# Space_Hexapod_hw_v1.net
KiCad netlist of a schematic drawn in EasyEDA Pro
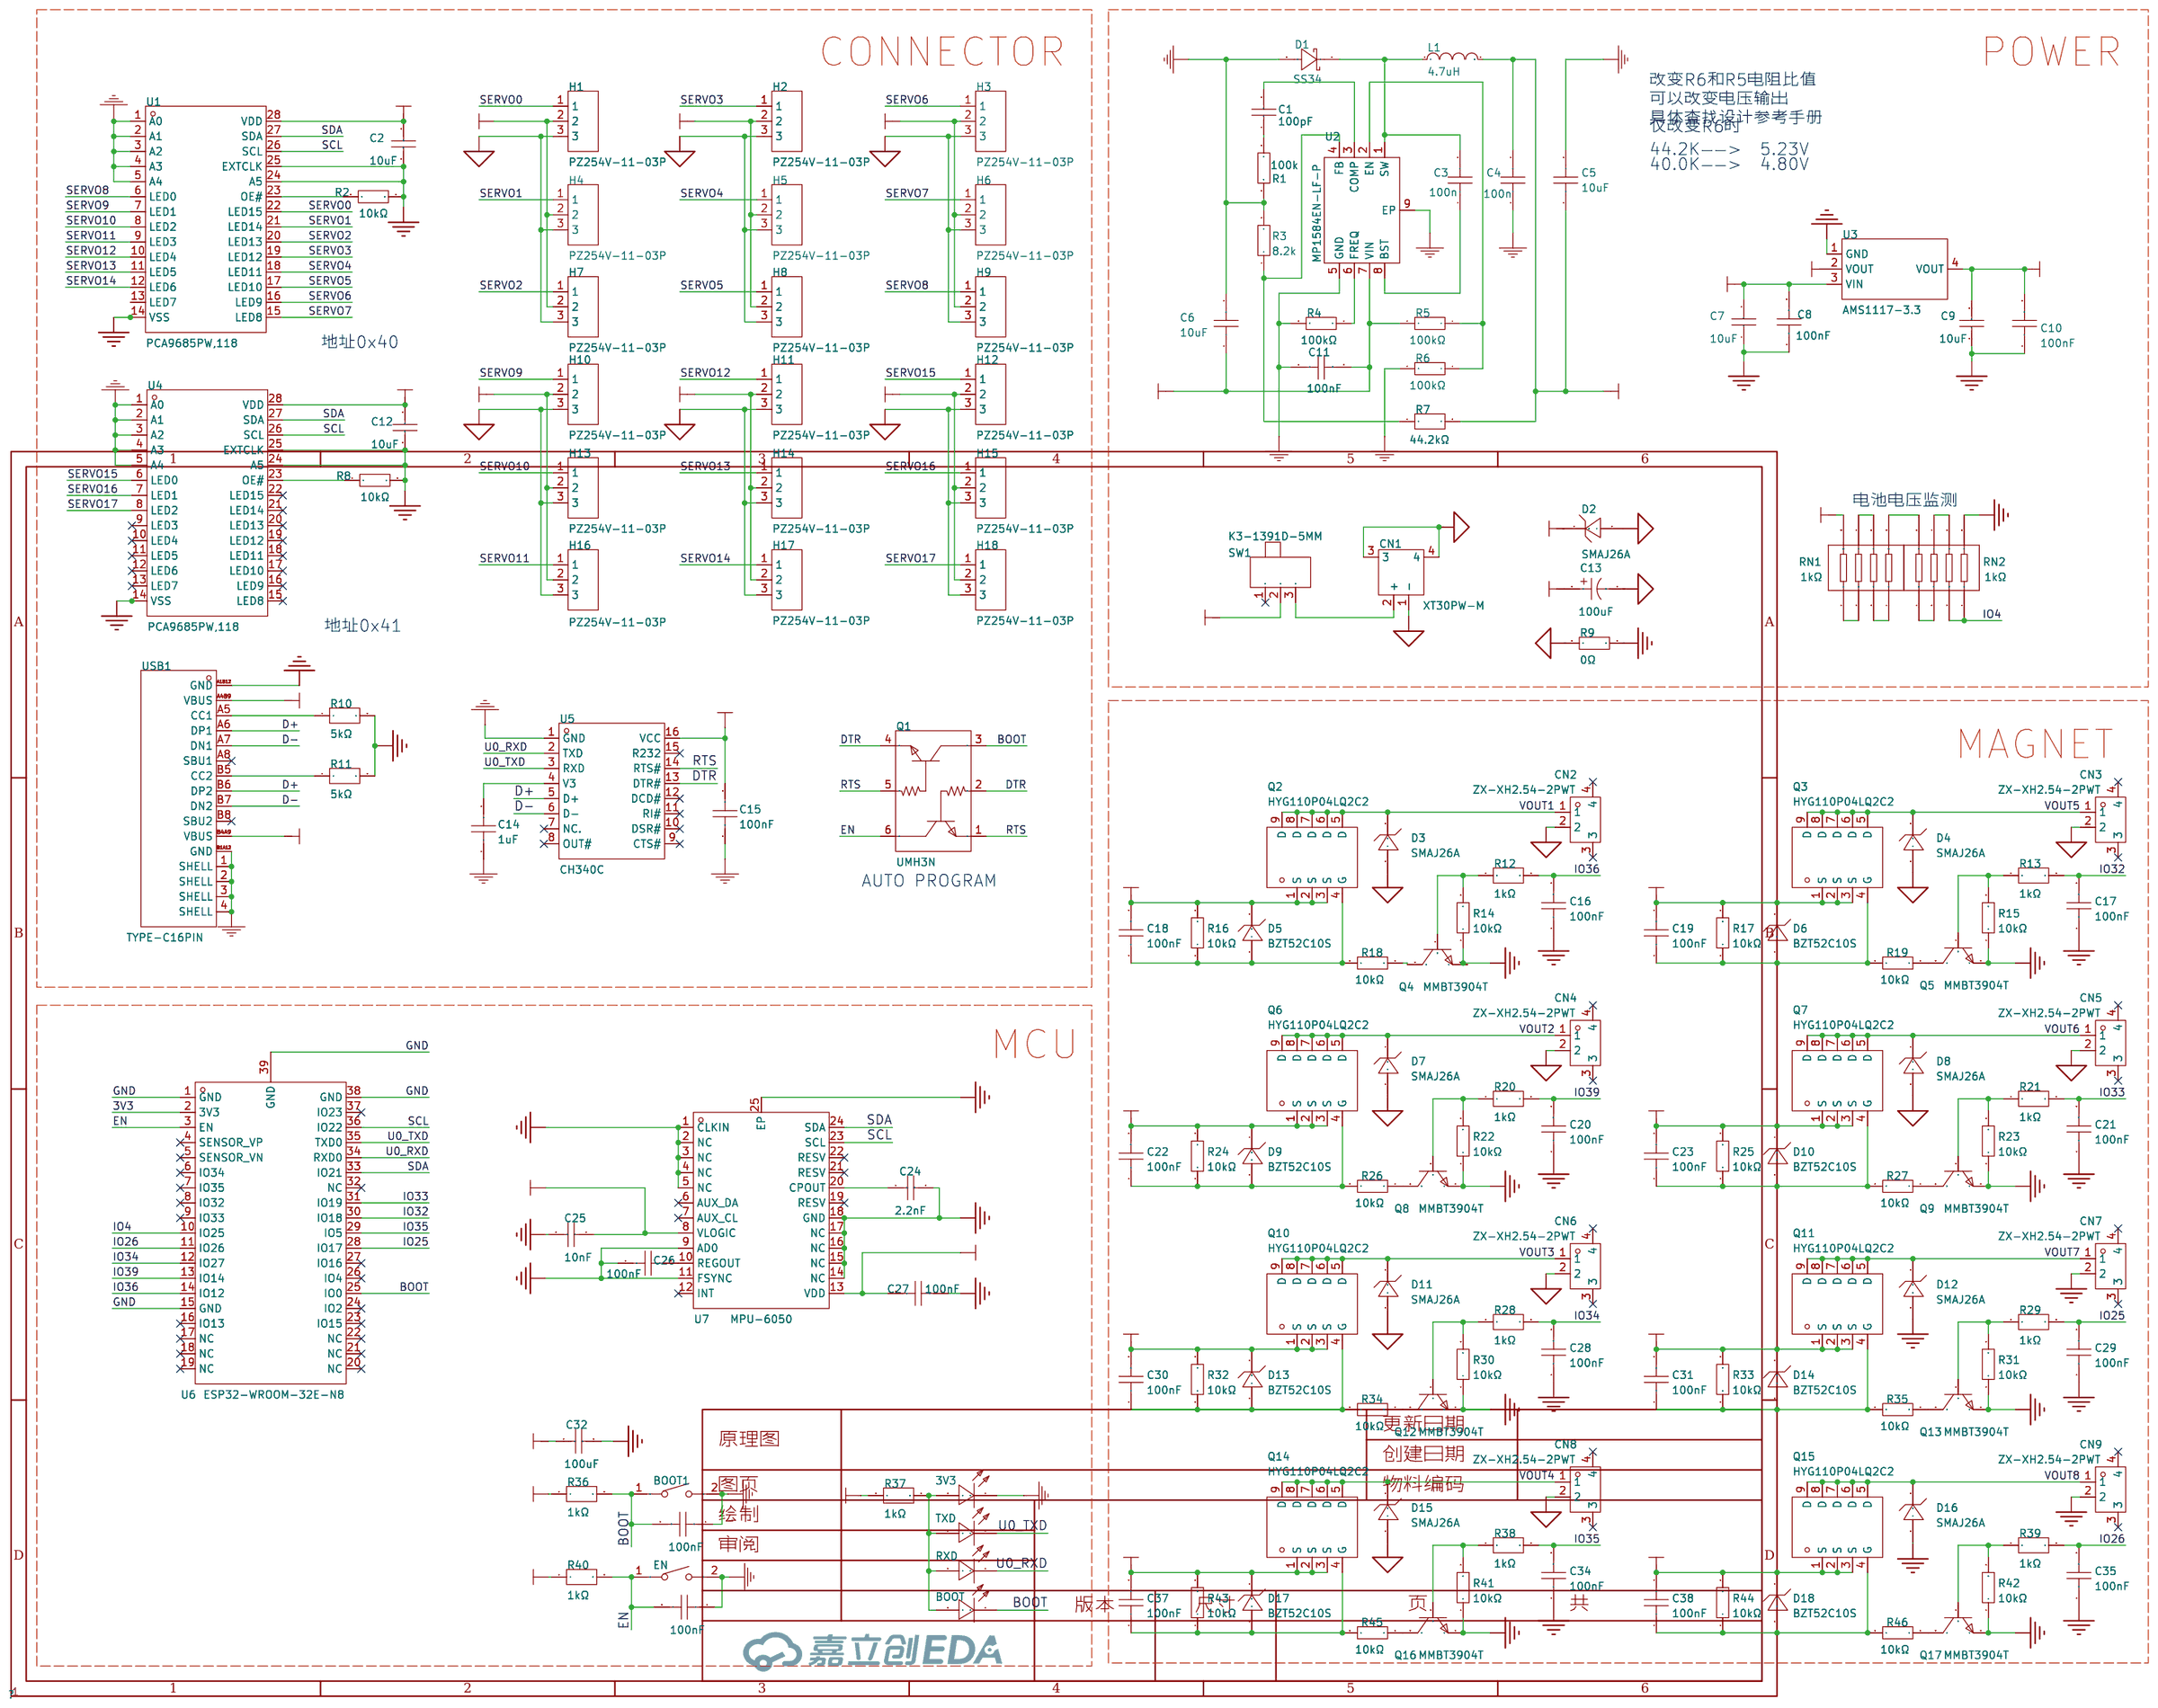
[diagram p0: schematic sheet]

(export (version "E")
  (design (tool "Eeschema 10.0.6"))
  (components
    (comp (ref "3V3")
      (value "NCD0402G1")
      (footprint "easyedapro:LED0402-RD")
      (fields (field (name "Manufacturer") "国星光电"))
      (libsource (lib "easyedapro") (part "FC-F1005UGK-520M5"))
    )
    (comp (ref "BOOT")
      (value "NCD0402G1")
      (footprint "easyedapro:LED0402-RD")
      (fields (field (name "Manufacturer") "国星光电"))
      (libsource (lib "easyedapro") (part "FC-F1005UGK-520M5"))
    )
    (comp (ref "BOOT1")
      (value "TS-1088-AR02016")
      (footprint "easyedapro:SW-SMD_L3.9-W3.0-P4.45")
      (fields (field (name "Manufacturer") "XUNPU(讯普)"))
      (libsource (lib "easyedapro") (part "TS-1088-AR02016"))
    )
    (comp (ref "C1")
      (value "100pF")
      (footprint "easyedapro:C0402")
      (description "容值:100pF;精度:±5%;额定电压:50V;材质(温度系数):C0G;")
      (fields
        (field (name "Manufacturer Part") "GRM1555C1H101JA01D")
        (field (name "Manufacturer") "muRata(村田)")
      )
      (libsource (lib "easyedapro") (part "GRM1555C1H101JA01D"))
    )
    (comp (ref "C2")
      (value "10uF")
      (footprint "easyedapro:C0402")
      (description "容值:10uF;精度:±20%;额定电压:6.3V;材质(温度系数):X5R;")
      (fields
        (field (name "Manufacturer Part") "CL05A106MQ5NUNC")
        (field (name "Manufacturer") "SAMSUNG(三星)")
      )
      (libsource (lib "easyedapro") (part "CL05A106MQ5NUNC"))
    )
    (comp (ref "C3")
      (value "100n")
      (footprint "easyedapro:C0402")
      (description "容值:100nF;精度:±10%;额定电压:50V;材质(温度系数):X7R;")
      (fields
        (field (name "Manufacturer Part") "CL05B104KB54PNC")
        (field (name "Manufacturer") "SAMSUNG(三星)")
      )
      (libsource (lib "easyedapro") (part "CL05B104KB54PNC"))
    )
    (comp (ref "C4")
      (value "100n")
      (footprint "easyedapro:C0402")
      (description "容值:100nF;精度:±10%;额定电压:50V;材质(温度系数):X7R;")
      (fields
        (field (name "Manufacturer Part") "CL05B104KB54PNC")
        (field (name "Manufacturer") "SAMSUNG(三星)")
      )
      (libsource (lib "easyedapro") (part "CL05B104KB54PNC"))
    )
    (comp (ref "C5")
      (value "10uF")
      (footprint "easyedapro:C1206")
      (description "容值:10uF;精度:±10%;额定电压:50V;温度系数:X5R;")
      (fields
        (field (name "Manufacturer Part") "HGC1206R5106K500NSPJ")
        (field (name "Manufacturer") "Chinocera(华瓷)")
      )
      (libsource (lib "easyedapro") (part "HGC1206R5106K500NSPJ"))
    )
    (comp (ref "C6")
      (value "10uF")
      (footprint "easyedapro:C1206")
      (description "容值:10uF;精度:±10%;额定电压:50V;温度系数:X5R;")
      (fields
        (field (name "Manufacturer Part") "HGC1206R5106K500NSPJ")
        (field (name "Manufacturer") "Chinocera(华瓷)")
      )
      (libsource (lib "easyedapro") (part "HGC1206R5106K500NSPJ"))
    )
    (comp (ref "C7")
      (value "10uF")
      (footprint "easyedapro:C0402")
      (description "容值:10uF;精度:±20%;额定电压:6.3V;材质(温度系数):X5R;")
      (fields
        (field (name "Manufacturer Part") "CL05A106MQ5NUNC")
        (field (name "Manufacturer") "SAMSUNG(三星)")
      )
      (libsource (lib "easyedapro") (part "CL05A106MQ5NUNC"))
    )
    (comp (ref "C8")
      (value "100nF")
      (footprint "easyedapro:C0402")
      (description "容值:100nF;精度:±10%;额定电压:16V;材质(温度系数):X7R;")
      (fields
        (field (name "Manufacturer Part") "CC0402KRX7R7BB104")
        (field (name "Manufacturer") "YAGEO(国巨)")
      )
      (libsource (lib "easyedapro") (part "CC0402KRX7R7BB104"))
    )
    (comp (ref "C9")
      (value "10uF")
      (footprint "easyedapro:C0402")
      (description "容值:10uF;精度:±20%;额定电压:6.3V;材质(温度系数):X5R;")
      (fields
        (field (name "Manufacturer Part") "CL05A106MQ5NUNC")
        (field (name "Manufacturer") "SAMSUNG(三星)")
      )
      (libsource (lib "easyedapro") (part "CL05A106MQ5NUNC"))
    )
    (comp (ref "C10")
      (value "100nF")
      (footprint "easyedapro:C0402")
      (description "容值:100nF;精度:±10%;额定电压:16V;材质(温度系数):X7R;")
      (fields
        (field (name "Manufacturer Part") "CC0402KRX7R7BB104")
        (field (name "Manufacturer") "YAGEO(国巨)")
      )
      (libsource (lib "easyedapro") (part "CC0402KRX7R7BB104"))
    )
    (comp (ref "C11")
      (value "100nF")
      (footprint "easyedapro:C0402")
      (description "容值:100nF;精度:±10%;额定电压:50V;材质(温度系数):X7R;")
      (fields
        (field (name "Manufacturer Part") "CL05B104KB54PNC")
        (field (name "Manufacturer") "SAMSUNG(三星)")
      )
      (libsource (lib "easyedapro") (part "CL05B104KB54PNC"))
    )
    (comp (ref "C12")
      (value "10uF")
      (footprint "easyedapro:C0402")
      (description "容值:10uF;精度:±20%;额定电压:6.3V;材质(温度系数):X5R;")
      (fields
        (field (name "Manufacturer Part") "CL05A106MQ5NUNC")
        (field (name "Manufacturer") "SAMSUNG(三星)")
      )
      (libsource (lib "easyedapro") (part "CL05A106MQ5NUNC"))
    )
    (comp (ref "C13")
      (value "100uF")
      (footprint "easyedapro:CAP-SMD_BD6.3-L6.6-W6.6-LS7.6-FD-1")
      (description "容值:100uF;精度:±20%;额定电压:35V;纹波电流:230mA@120Hz;等效串联电阻:600mΩ@100kHz;")
      (fields
        (field (name "Manufacturer Part") "RVE100UF35V67RV0072")
        (field (name "Manufacturer") "KNSCHA(科尼盛)")
      )
      (libsource (lib "easyedapro") (part "RVE100UF35V67RV0072"))
    )
    (comp (ref "C14")
      (value "1uF")
      (footprint "easyedapro:C0402")
      (description "容值:1uF;精度:±10%;额定电压:50V;材质(温度系数):X5R;")
      (fields
        (field (name "Manufacturer Part") "GRM155R61H105KE05D")
        (field (name "Manufacturer") "muRata(村田)")
      )
      (libsource (lib "easyedapro") (part "GRM155R61H105KE05D"))
    )
    (comp (ref "C15")
      (value "100nF")
      (footprint "easyedapro:C0402")
      (description "容值:100nF;精度:±10%;额定电压:50V;材质(温度系数):X7R;")
      (fields
        (field (name "Manufacturer Part") "CL05B104KB54PNC")
        (field (name "Manufacturer") "SAMSUNG(三星)")
      )
      (libsource (lib "easyedapro") (part "CL05B104KB54PNC"))
    )
    (comp (ref "C16")
      (value "100nF")
      (footprint "easyedapro:C0402")
      (description "容值:100nF;精度:±10%;额定电压:50V;材质(温度系数):X7R;")
      (fields
        (field (name "Manufacturer Part") "CL05B104KB54PNC")
        (field (name "Manufacturer") "SAMSUNG(三星)")
      )
      (libsource (lib "easyedapro") (part "CL05B104KB54PNC"))
    )
    (comp (ref "C17")
      (value "100nF")
      (footprint "easyedapro:C0402")
      (description "容值:100nF;精度:±10%;额定电压:50V;材质(温度系数):X7R;")
      (fields
        (field (name "Manufacturer Part") "CL05B104KB54PNC")
        (field (name "Manufacturer") "SAMSUNG(三星)")
      )
      (libsource (lib "easyedapro") (part "CL05B104KB54PNC"))
    )
    (comp (ref "C18")
      (value "100nF")
      (footprint "easyedapro:C0402")
      (description "容值:100nF;精度:±10%;额定电压:50V;材质(温度系数):X7R;")
      (fields
        (field (name "Manufacturer Part") "CL05B104KB54PNC")
        (field (name "Manufacturer") "SAMSUNG(三星)")
      )
      (libsource (lib "easyedapro") (part "CL05B104KB54PNC"))
    )
    (comp (ref "C19")
      (value "100nF")
      (footprint "easyedapro:C0402")
      (description "容值:100nF;精度:±10%;额定电压:50V;材质(温度系数):X7R;")
      (fields
        (field (name "Manufacturer Part") "CL05B104KB54PNC")
        (field (name "Manufacturer") "SAMSUNG(三星)")
      )
      (libsource (lib "easyedapro") (part "CL05B104KB54PNC"))
    )
    (comp (ref "C20")
      (value "100nF")
      (footprint "easyedapro:C0402")
      (description "容值:100nF;精度:±10%;额定电压:50V;材质(温度系数):X7R;")
      (fields
        (field (name "Manufacturer Part") "CL05B104KB54PNC")
        (field (name "Manufacturer") "SAMSUNG(三星)")
      )
      (libsource (lib "easyedapro") (part "CL05B104KB54PNC"))
    )
    (comp (ref "C21")
      (value "100nF")
      (footprint "easyedapro:C0402")
      (description "容值:100nF;精度:±10%;额定电压:50V;材质(温度系数):X7R;")
      (fields
        (field (name "Manufacturer Part") "CL05B104KB54PNC")
        (field (name "Manufacturer") "SAMSUNG(三星)")
      )
      (libsource (lib "easyedapro") (part "CL05B104KB54PNC"))
    )
    (comp (ref "C22")
      (value "100nF")
      (footprint "easyedapro:C0402")
      (description "容值:100nF;精度:±10%;额定电压:50V;材质(温度系数):X7R;")
      (fields
        (field (name "Manufacturer Part") "CL05B104KB54PNC")
        (field (name "Manufacturer") "SAMSUNG(三星)")
      )
      (libsource (lib "easyedapro") (part "CL05B104KB54PNC"))
    )
    (comp (ref "C23")
      (value "100nF")
      (footprint "easyedapro:C0402")
      (description "容值:100nF;精度:±10%;额定电压:50V;材质(温度系数):X7R;")
      (fields
        (field (name "Manufacturer Part") "CL05B104KB54PNC")
        (field (name "Manufacturer") "SAMSUNG(三星)")
      )
      (libsource (lib "easyedapro") (part "CL05B104KB54PNC"))
    )
    (comp (ref "C24")
      (value "2.2nF")
      (footprint "easyedapro:C0402")
      (description "容值:2.2nF;精度:±10%;额定电压:50V;材质(温度系数):X7R;")
      (fields
        (field (name "Manufacturer Part") "CC0402KRX7R9BB222")
        (field (name "Manufacturer") "YAGEO(国巨)")
      )
      (libsource (lib "easyedapro") (part "CC0402KRX7R9BB222"))
    )
    (comp (ref "C25")
      (value "10nF")
      (footprint "easyedapro:C0402")
      (description "容值:10nF;精度:±10%;额定电压:50V;材质(温度系数):X7R;")
      (fields
        (field (name "Manufacturer Part") "CL05B103KB5NNNC")
        (field (name "Manufacturer") "SAMSUNG(三星)")
      )
      (libsource (lib "easyedapro") (part "CL05B103KB5NNNC"))
    )
    (comp (ref "C26")
      (value "100nF")
      (footprint "easyedapro:C0402")
      (description "容值:100nF;精度:±10%;额定电压:50V;材质(温度系数):X7R;")
      (fields
        (field (name "Manufacturer Part") "CL05B104KB54PNC")
        (field (name "Manufacturer") "SAMSUNG(三星)")
      )
      (libsource (lib "easyedapro") (part "CL05B104KB54PNC"))
    )
    (comp (ref "C27")
      (value "100nF")
      (footprint "easyedapro:C0402")
      (description "容值:100nF;精度:±10%;额定电压:50V;材质(温度系数):X7R;")
      (fields
        (field (name "Manufacturer Part") "CL05B104KB54PNC")
        (field (name "Manufacturer") "SAMSUNG(三星)")
      )
      (libsource (lib "easyedapro") (part "CL05B104KB54PNC"))
    )
    (comp (ref "C28")
      (value "100nF")
      (footprint "easyedapro:C0402")
      (description "容值:100nF;精度:±10%;额定电压:50V;材质(温度系数):X7R;")
      (fields
        (field (name "Manufacturer Part") "CL05B104KB54PNC")
        (field (name "Manufacturer") "SAMSUNG(三星)")
      )
      (libsource (lib "easyedapro") (part "CL05B104KB54PNC"))
    )
    (comp (ref "C29")
      (value "100nF")
      (footprint "easyedapro:C0402")
      (description "容值:100nF;精度:±10%;额定电压:50V;材质(温度系数):X7R;")
      (fields
        (field (name "Manufacturer Part") "CL05B104KB54PNC")
        (field (name "Manufacturer") "SAMSUNG(三星)")
      )
      (libsource (lib "easyedapro") (part "CL05B104KB54PNC"))
    )
    (comp (ref "C30")
      (value "100nF")
      (footprint "easyedapro:C0402")
      (description "容值:100nF;精度:±10%;额定电压:50V;材质(温度系数):X7R;")
      (fields
        (field (name "Manufacturer Part") "CL05B104KB54PNC")
        (field (name "Manufacturer") "SAMSUNG(三星)")
      )
      (libsource (lib "easyedapro") (part "CL05B104KB54PNC"))
    )
    (comp (ref "C31")
      (value "100nF")
      (footprint "easyedapro:C0402")
      (description "容值:100nF;精度:±10%;额定电压:50V;材质(温度系数):X7R;")
      (fields
        (field (name "Manufacturer Part") "CL05B104KB54PNC")
        (field (name "Manufacturer") "SAMSUNG(三星)")
      )
      (libsource (lib "easyedapro") (part "CL05B104KB54PNC"))
    )
    (comp (ref "C32")
      (value "100uF")
      (footprint "easyedapro:C1206")
      (description "容值:100uF;精度:±20%;额定电压:6.3V;材质(温度系数):X5R;")
      (fields
        (field (name "Manufacturer Part") "CL31A107MQHNNNE")
        (field (name "Manufacturer") "SAMSUNG(三星)")
      )
      (libsource (lib "easyedapro") (part "CL31A107MQHNNNE"))
    )
    (comp (ref "C33")
      (value "100nF")
      (footprint "easyedapro:C0402")
      (description "容值:100nF;精度:±10%;额定电压:16V;材质(温度系数):X7R;")
      (fields
        (field (name "Manufacturer Part") "CC0402KRX7R7BB104")
        (field (name "Manufacturer") "YAGEO(国巨)")
      )
      (libsource (lib "easyedapro") (part "CC0402KRX7R7BB104"))
    )
    (comp (ref "C34")
      (value "100nF")
      (footprint "easyedapro:C0402")
      (description "容值:100nF;精度:±10%;额定电压:50V;材质(温度系数):X7R;")
      (fields
        (field (name "Manufacturer Part") "CL05B104KB54PNC")
        (field (name "Manufacturer") "SAMSUNG(三星)")
      )
      (libsource (lib "easyedapro") (part "CL05B104KB54PNC"))
    )
    (comp (ref "C35")
      (value "100nF")
      (footprint "easyedapro:C0402")
      (description "容值:100nF;精度:±10%;额定电压:50V;材质(温度系数):X7R;")
      (fields
        (field (name "Manufacturer Part") "CL05B104KB54PNC")
        (field (name "Manufacturer") "SAMSUNG(三星)")
      )
      (libsource (lib "easyedapro") (part "CL05B104KB54PNC"))
    )
    (comp (ref "C36")
      (value "100nF")
      (footprint "easyedapro:C0402")
      (description "容值:100nF;精度:±10%;额定电压:16V;材质(温度系数):X7R;")
      (fields
        (field (name "Manufacturer Part") "CC0402KRX7R7BB104")
        (field (name "Manufacturer") "YAGEO(国巨)")
      )
      (libsource (lib "easyedapro") (part "CC0402KRX7R7BB104"))
    )
    (comp (ref "C37")
      (value "100nF")
      (footprint "easyedapro:C0402")
      (description "容值:100nF;精度:±10%;额定电压:50V;材质(温度系数):X7R;")
      (fields
        (field (name "Manufacturer Part") "CL05B104KB54PNC")
        (field (name "Manufacturer") "SAMSUNG(三星)")
      )
      (libsource (lib "easyedapro") (part "CL05B104KB54PNC"))
    )
    (comp (ref "C38")
      (value "100nF")
      (footprint "easyedapro:C0402")
      (description "容值:100nF;精度:±10%;额定电压:50V;材质(温度系数):X7R;")
      (fields
        (field (name "Manufacturer Part") "CL05B104KB54PNC")
        (field (name "Manufacturer") "SAMSUNG(三星)")
      )
      (libsource (lib "easyedapro") (part "CL05B104KB54PNC"))
    )
    (comp (ref "CN1")
      (value "XT30PW-M")
      (footprint "easyedapro:CONN-TH_XT30PW-M")
      (description "Socket,DCsupply,XT30,male,PIN:2")
      (fields (field (name "Manufacturer") "AMASS(艾迈斯)"))
      (libsource (lib "easyedapro") (part "XT30PW-M"))
    )
    (comp (ref "CN2")
      (value "ZX-XH2.54-2PWT")
      (footprint "easyedapro:CONN-SMD_2P-P2.54_MEGASTAR_ZX-XH2.54-2PWT")
      (description "插针结构:1x2P;间距:2.5mm;安装方式:卧贴;参考系列:XH;总PIN数:2P;排数:1;每排PIN数:2;行距:-;额定电流:-;触头材质:黄铜;触头镀层:锡;工作温度范围:-;")
      (fields (field (name "Manufacturer") "Megastar(兆星)"))
      (libsource (lib "easyedapro") (part "ZX-XH2.54-2PWT"))
    )
    (comp (ref "CN3")
      (value "ZX-XH2.54-2PWT")
      (footprint "easyedapro:CONN-SMD_2P-P2.54_MEGASTAR_ZX-XH2.54-2PWT")
      (description "插针结构:1x2P;间距:2.5mm;安装方式:卧贴;参考系列:XH;总PIN数:2P;排数:1;每排PIN数:2;行距:-;额定电流:-;触头材质:黄铜;触头镀层:锡;工作温度范围:-;")
      (fields (field (name "Manufacturer") "Megastar(兆星)"))
      (libsource (lib "easyedapro") (part "ZX-XH2.54-2PWT"))
    )
    (comp (ref "CN4")
      (value "ZX-XH2.54-2PWT")
      (footprint "easyedapro:CONN-SMD_2P-P2.54_MEGASTAR_ZX-XH2.54-2PWT")
      (description "插针结构:1x2P;间距:2.5mm;安装方式:卧贴;参考系列:XH;总PIN数:2P;排数:1;每排PIN数:2;行距:-;额定电流:-;触头材质:黄铜;触头镀层:锡;工作温度范围:-;")
      (fields (field (name "Manufacturer") "Megastar(兆星)"))
      (libsource (lib "easyedapro") (part "ZX-XH2.54-2PWT"))
    )
    (comp (ref "CN5")
      (value "ZX-XH2.54-2PWT")
      (footprint "easyedapro:CONN-SMD_2P-P2.54_MEGASTAR_ZX-XH2.54-2PWT")
      (description "插针结构:1x2P;间距:2.5mm;安装方式:卧贴;参考系列:XH;总PIN数:2P;排数:1;每排PIN数:2;行距:-;额定电流:-;触头材质:黄铜;触头镀层:锡;工作温度范围:-;")
      (fields (field (name "Manufacturer") "Megastar(兆星)"))
      (libsource (lib "easyedapro") (part "ZX-XH2.54-2PWT"))
    )
    (comp (ref "CN6")
      (value "ZX-XH2.54-2PWT")
      (footprint "easyedapro:CONN-SMD_2P-P2.54_MEGASTAR_ZX-XH2.54-2PWT")
      (description "插针结构:1x2P;间距:2.5mm;安装方式:卧贴;参考系列:XH;总PIN数:2P;排数:1;每排PIN数:2;行距:-;额定电流:-;触头材质:黄铜;触头镀层:锡;工作温度范围:-;")
      (fields (field (name "Manufacturer") "Megastar(兆星)"))
      (libsource (lib "easyedapro") (part "ZX-XH2.54-2PWT"))
    )
    (comp (ref "CN7")
      (value "ZX-XH2.54-2PWT")
      (footprint "easyedapro:CONN-SMD_2P-P2.54_MEGASTAR_ZX-XH2.54-2PWT")
      (description "插针结构:1x2P;间距:2.5mm;安装方式:卧贴;参考系列:XH;总PIN数:2P;排数:1;每排PIN数:2;行距:-;额定电流:-;触头材质:黄铜;触头镀层:锡;工作温度范围:-;")
      (fields (field (name "Manufacturer") "Megastar(兆星)"))
      (libsource (lib "easyedapro") (part "ZX-XH2.54-2PWT"))
    )
    (comp (ref "CN8")
      (value "ZX-XH2.54-2PWT")
      (footprint "easyedapro:CONN-SMD_2P-P2.54_MEGASTAR_ZX-XH2.54-2PWT")
      (description "插针结构:1x2P;间距:2.5mm;安装方式:卧贴;参考系列:XH;总PIN数:2P;排数:1;每排PIN数:2;行距:-;额定电流:-;触头材质:黄铜;触头镀层:锡;工作温度范围:-;")
      (fields (field (name "Manufacturer") "Megastar(兆星)"))
      (libsource (lib "easyedapro") (part "ZX-XH2.54-2PWT"))
    )
    (comp (ref "CN9")
      (value "ZX-XH2.54-2PWT")
      (footprint "easyedapro:CONN-SMD_2P-P2.54_MEGASTAR_ZX-XH2.54-2PWT")
      (description "插针结构:1x2P;间距:2.5mm;安装方式:卧贴;参考系列:XH;总PIN数:2P;排数:1;每排PIN数:2;行距:-;额定电流:-;触头材质:黄铜;触头镀层:锡;工作温度范围:-;")
      (fields (field (name "Manufacturer") "Megastar(兆星)"))
      (libsource (lib "easyedapro") (part "ZX-XH2.54-2PWT"))
    )
    (comp (ref "D1")
      (value "SS34")
      (footprint "easyedapro:SMA_L4.2-W2.7-LS5.0-RD")
      (description "二极管配置:-;正向压降(Vf):550mV@3A;直流反向耐压(Vr):40V;平均整流电流(Io):3A;")
      (fields (field (name "Manufacturer") "KUU"))
      (libsource (lib "easyedapro") (part "SS34_C2891718"))
    )
    (comp (ref "D2")
      (value "SMAJ26A")
      (footprint "easyedapro:SMA_L4.3-W2.6-LS5.1-RD")
      (description "反向截止电压(Vrwm):26V;最大钳位电压:42.1V;峰值脉冲电流(Ipp)@10/1000us:9.5A;击穿电压:28.9V;")
      (fields (field (name "Manufacturer") "GOODWORK(固得沃克)"))
      (libsource (lib "easyedapro") (part "SMAJ26A_C2848697"))
    )
    (comp (ref "D3")
      (value "SMAJ26A")
      (footprint "easyedapro:SMA_L4.3-W2.6-LS5.1-RD")
      (description "反向截止电压(Vrwm):26V;最大钳位电压:42.1V;峰值脉冲电流(Ipp)@10/1000us:9.5A;击穿电压:28.9V;")
      (fields (field (name "Manufacturer") "GOODWORK(固得沃克)"))
      (libsource (lib "easyedapro") (part "SMAJ26A_C2848697"))
    )
    (comp (ref "D4")
      (value "SMAJ26A")
      (footprint "easyedapro:SMA_L4.3-W2.6-LS5.1-RD")
      (description "反向截止电压(Vrwm):26V;最大钳位电压:42.1V;峰值脉冲电流(Ipp)@10/1000us:9.5A;击穿电压:28.9V;")
      (fields (field (name "Manufacturer") "GOODWORK(固得沃克)"))
      (libsource (lib "easyedapro") (part "SMAJ26A_C2848697"))
    )
    (comp (ref "D5")
      (value "BZT52C10S")
      (footprint "easyedapro:SOD-323_L1.6-W1.3-LS2.7-RD")
      (description "二极管配置:独立式;稳压值(标称值):10V;稳压值(范围):9.4V~10.6V;功率:200mW;精度:-;")
      (fields (field (name "Manufacturer") "晶导微电子"))
      (libsource (lib "easyedapro") (part "BZT52C10S_C353563"))
    )
    (comp (ref "D6")
      (value "BZT52C10S")
      (footprint "easyedapro:SOD-323_L1.6-W1.3-LS2.7-RD")
      (description "二极管配置:独立式;稳压值(标称值):10V;稳压值(范围):9.4V~10.6V;功率:200mW;精度:-;")
      (fields (field (name "Manufacturer") "晶导微电子"))
      (libsource (lib "easyedapro") (part "BZT52C10S_C353563"))
    )
    (comp (ref "D7")
      (value "SMAJ26A")
      (footprint "easyedapro:SMA_L4.3-W2.6-LS5.1-RD")
      (description "反向截止电压(Vrwm):26V;最大钳位电压:42.1V;峰值脉冲电流(Ipp)@10/1000us:9.5A;击穿电压:28.9V;")
      (fields (field (name "Manufacturer") "GOODWORK(固得沃克)"))
      (libsource (lib "easyedapro") (part "SMAJ26A_C2848697"))
    )
    (comp (ref "D8")
      (value "SMAJ26A")
      (footprint "easyedapro:SMA_L4.3-W2.6-LS5.1-RD")
      (description "反向截止电压(Vrwm):26V;最大钳位电压:42.1V;峰值脉冲电流(Ipp)@10/1000us:9.5A;击穿电压:28.9V;")
      (fields (field (name "Manufacturer") "GOODWORK(固得沃克)"))
      (libsource (lib "easyedapro") (part "SMAJ26A_C2848697"))
    )
    (comp (ref "D9")
      (value "BZT52C10S")
      (footprint "easyedapro:SOD-323_L1.6-W1.3-LS2.7-RD")
      (description "二极管配置:独立式;稳压值(标称值):10V;稳压值(范围):9.4V~10.6V;功率:200mW;精度:-;")
      (fields (field (name "Manufacturer") "晶导微电子"))
      (libsource (lib "easyedapro") (part "BZT52C10S_C353563"))
    )
    (comp (ref "D10")
      (value "BZT52C10S")
      (footprint "easyedapro:SOD-323_L1.6-W1.3-LS2.7-RD")
      (description "二极管配置:独立式;稳压值(标称值):10V;稳压值(范围):9.4V~10.6V;功率:200mW;精度:-;")
      (fields (field (name "Manufacturer") "晶导微电子"))
      (libsource (lib "easyedapro") (part "BZT52C10S_C353563"))
    )
    (comp (ref "D11")
      (value "SMAJ26A")
      (footprint "easyedapro:SMA_L4.3-W2.6-LS5.1-RD")
      (description "反向截止电压(Vrwm):26V;最大钳位电压:42.1V;峰值脉冲电流(Ipp)@10/1000us:9.5A;击穿电压:28.9V;")
      (fields (field (name "Manufacturer") "GOODWORK(固得沃克)"))
      (libsource (lib "easyedapro") (part "SMAJ26A_C2848697"))
    )
    (comp (ref "D12")
      (value "SMAJ26A")
      (footprint "easyedapro:SMA_L4.3-W2.6-LS5.1-RD")
      (description "反向截止电压(Vrwm):26V;最大钳位电压:42.1V;峰值脉冲电流(Ipp)@10/1000us:9.5A;击穿电压:28.9V;")
      (fields (field (name "Manufacturer") "GOODWORK(固得沃克)"))
      (libsource (lib "easyedapro") (part "SMAJ26A_C2848697"))
    )
    (comp (ref "D13")
      (value "BZT52C10S")
      (footprint "easyedapro:SOD-323_L1.6-W1.3-LS2.7-RD")
      (description "二极管配置:独立式;稳压值(标称值):10V;稳压值(范围):9.4V~10.6V;功率:200mW;精度:-;")
      (fields (field (name "Manufacturer") "晶导微电子"))
      (libsource (lib "easyedapro") (part "BZT52C10S_C353563"))
    )
    (comp (ref "D14")
      (value "BZT52C10S")
      (footprint "easyedapro:SOD-323_L1.6-W1.3-LS2.7-RD")
      (description "二极管配置:独立式;稳压值(标称值):10V;稳压值(范围):9.4V~10.6V;功率:200mW;精度:-;")
      (fields (field (name "Manufacturer") "晶导微电子"))
      (libsource (lib "easyedapro") (part "BZT52C10S_C353563"))
    )
    (comp (ref "D15")
      (value "SMAJ26A")
      (footprint "easyedapro:SMA_L4.3-W2.6-LS5.1-RD")
      (description "反向截止电压(Vrwm):26V;最大钳位电压:42.1V;峰值脉冲电流(Ipp)@10/1000us:9.5A;击穿电压:28.9V;")
      (fields (field (name "Manufacturer") "GOODWORK(固得沃克)"))
      (libsource (lib "easyedapro") (part "SMAJ26A_C2848697"))
    )
    (comp (ref "D16")
      (value "SMAJ26A")
      (footprint "easyedapro:SMA_L4.3-W2.6-LS5.1-RD")
      (description "反向截止电压(Vrwm):26V;最大钳位电压:42.1V;峰值脉冲电流(Ipp)@10/1000us:9.5A;击穿电压:28.9V;")
      (fields (field (name "Manufacturer") "GOODWORK(固得沃克)"))
      (libsource (lib "easyedapro") (part "SMAJ26A_C2848697"))
    )
    (comp (ref "D17")
      (value "BZT52C10S")
      (footprint "easyedapro:SOD-323_L1.6-W1.3-LS2.7-RD")
      (description "二极管配置:独立式;稳压值(标称值):10V;稳压值(范围):9.4V~10.6V;功率:200mW;精度:-;")
      (fields (field (name "Manufacturer") "晶导微电子"))
      (libsource (lib "easyedapro") (part "BZT52C10S_C353563"))
    )
    (comp (ref "D18")
      (value "BZT52C10S")
      (footprint "easyedapro:SOD-323_L1.6-W1.3-LS2.7-RD")
      (description "二极管配置:独立式;稳压值(标称值):10V;稳压值(范围):9.4V~10.6V;功率:200mW;精度:-;")
      (fields (field (name "Manufacturer") "晶导微电子"))
      (libsource (lib "easyedapro") (part "BZT52C10S_C353563"))
    )
    (comp (ref "EN")
      (value "TS-1088-AR02016")
      (footprint "easyedapro:SW-SMD_L3.9-W3.0-P4.45")
      (fields (field (name "Manufacturer") "XUNPU(讯普)"))
      (libsource (lib "easyedapro") (part "TS-1088-AR02016"))
    )
    (comp (ref "H1")
      (value "PZ254V-11-03P")
      (footprint "easyedapro:HDR-TH_3P-P2.54-V-M")
      (fields (field (name "Manufacturer") "XFCN(兴飞)"))
      (libsource (lib "easyedapro") (part "PZ254V-11-03P_C2937625"))
    )
    (comp (ref "H2")
      (value "PZ254V-11-03P")
      (footprint "easyedapro:HDR-TH_3P-P2.54-V-M")
      (fields (field (name "Manufacturer") "XFCN(兴飞)"))
      (libsource (lib "easyedapro") (part "PZ254V-11-03P_C2937625"))
    )
    (comp (ref "H3")
      (value "PZ254V-11-03P")
      (footprint "easyedapro:HDR-TH_3P-P2.54-V-M")
      (fields (field (name "Manufacturer") "XFCN(兴飞)"))
      (libsource (lib "easyedapro") (part "PZ254V-11-03P_C2937625"))
    )
    (comp (ref "H4")
      (value "PZ254V-11-03P")
      (footprint "easyedapro:HDR-TH_3P-P2.54-V-M")
      (fields (field (name "Manufacturer") "XFCN(兴飞)"))
      (libsource (lib "easyedapro") (part "PZ254V-11-03P_C2937625"))
    )
    (comp (ref "H5")
      (value "PZ254V-11-03P")
      (footprint "easyedapro:HDR-TH_3P-P2.54-V-M")
      (fields (field (name "Manufacturer") "XFCN(兴飞)"))
      (libsource (lib "easyedapro") (part "PZ254V-11-03P_C2937625"))
    )
    (comp (ref "H6")
      (value "PZ254V-11-03P")
      (footprint "easyedapro:HDR-TH_3P-P2.54-V-M")
      (fields (field (name "Manufacturer") "XFCN(兴飞)"))
      (libsource (lib "easyedapro") (part "PZ254V-11-03P_C2937625"))
    )
    (comp (ref "H7")
      (value "PZ254V-11-03P")
      (footprint "easyedapro:HDR-TH_3P-P2.54-V-M")
      (fields (field (name "Manufacturer") "XFCN(兴飞)"))
      (libsource (lib "easyedapro") (part "PZ254V-11-03P_C2937625"))
    )
    (comp (ref "H8")
      (value "PZ254V-11-03P")
      (footprint "easyedapro:HDR-TH_3P-P2.54-V-M")
      (fields (field (name "Manufacturer") "XFCN(兴飞)"))
      (libsource (lib "easyedapro") (part "PZ254V-11-03P_C2937625"))
    )
    (comp (ref "H9")
      (value "PZ254V-11-03P")
      (footprint "easyedapro:HDR-TH_3P-P2.54-V-M")
      (fields (field (name "Manufacturer") "XFCN(兴飞)"))
      (libsource (lib "easyedapro") (part "PZ254V-11-03P_C2937625"))
    )
    (comp (ref "H10")
      (value "PZ254V-11-03P")
      (footprint "easyedapro:HDR-TH_3P-P2.54-V-M")
      (fields (field (name "Manufacturer") "XFCN(兴飞)"))
      (libsource (lib "easyedapro") (part "PZ254V-11-03P_C2937625"))
    )
    (comp (ref "H11")
      (value "PZ254V-11-03P")
      (footprint "easyedapro:HDR-TH_3P-P2.54-V-M")
      (fields (field (name "Manufacturer") "XFCN(兴飞)"))
      (libsource (lib "easyedapro") (part "PZ254V-11-03P_C2937625"))
    )
    (comp (ref "H12")
      (value "PZ254V-11-03P")
      (footprint "easyedapro:HDR-TH_3P-P2.54-V-M")
      (fields (field (name "Manufacturer") "XFCN(兴飞)"))
      (libsource (lib "easyedapro") (part "PZ254V-11-03P_C2937625"))
    )
    (comp (ref "H13")
      (value "PZ254V-11-03P")
      (footprint "easyedapro:HDR-TH_3P-P2.54-V-M")
      (fields (field (name "Manufacturer") "XFCN(兴飞)"))
      (libsource (lib "easyedapro") (part "PZ254V-11-03P_C2937625"))
    )
    (comp (ref "H14")
      (value "PZ254V-11-03P")
      (footprint "easyedapro:HDR-TH_3P-P2.54-V-M")
      (fields (field (name "Manufacturer") "XFCN(兴飞)"))
      (libsource (lib "easyedapro") (part "PZ254V-11-03P_C2937625"))
    )
    (comp (ref "H15")
      (value "PZ254V-11-03P")
      (footprint "easyedapro:HDR-TH_3P-P2.54-V-M")
      (fields (field (name "Manufacturer") "XFCN(兴飞)"))
      (libsource (lib "easyedapro") (part "PZ254V-11-03P_C2937625"))
    )
    (comp (ref "H16")
      (value "PZ254V-11-03P")
      (footprint "easyedapro:HDR-TH_3P-P2.54-V-M")
      (fields (field (name "Manufacturer") "XFCN(兴飞)"))
      (libsource (lib "easyedapro") (part "PZ254V-11-03P_C2937625"))
    )
    (comp (ref "H17")
      (value "PZ254V-11-03P")
      (footprint "easyedapro:HDR-TH_3P-P2.54-V-M")
      (fields (field (name "Manufacturer") "XFCN(兴飞)"))
      (libsource (lib "easyedapro") (part "PZ254V-11-03P_C2937625"))
    )
    (comp (ref "H18")
      (value "PZ254V-11-03P")
      (footprint "easyedapro:HDR-TH_3P-P2.54-V-M")
      (fields (field (name "Manufacturer") "XFCN(兴飞)"))
      (libsource (lib "easyedapro") (part "PZ254V-11-03P_C2937625"))
    )
    (comp (ref "L1")
      (value "4.7uH")
      (footprint "easyedapro:IND-SMD_L5.9-W5.2")
      (description "电感值:4.7uH;精度:±20%;额定电流:3A;")
      (fields
        (field (name "Manufacturer Part") "MAPM0530F-4R7M-LF")
        (field (name "Manufacturer") "microgate(麦捷科技)")
      )
      (libsource (lib "easyedapro") (part "MAPM0530F-4R7M-LF"))
    )
    (comp (ref "Q1")
      (value "UMH3N")
      (footprint "easyedapro:SC-70-6_L2.2-W1.3-P0.65-LS2.1-BR")
      (description "晶体管类型:-;集射极击穿电压(Vceo):50V;集电极电流(Ic):100mA;功率(Pd):150mW;直流电流增益(hFE@Ic,Vce):100@1mA,5V;")
      (fields (field (name "Manufacturer") "CJ(江苏长电/长晶)"))
      (libsource (lib "easyedapro") (part "UMH3N"))
    )
    (comp (ref "Q2")
      (value "HYG110P04LQ2C2")
      (footprint "easyedapro:PDFN-8_L5.2-W5.9-P1.27-LS6.2-BL")
      (fields (field (name "Manufacturer") "HUAYI(华羿微)"))
      (libsource (lib "easyedapro") (part "HYG110P04LQ2C2"))
    )
    (comp (ref "Q3")
      (value "HYG110P04LQ2C2")
      (footprint "easyedapro:PDFN-8_L5.2-W5.9-P1.27-LS6.2-BL")
      (fields (field (name "Manufacturer") "HUAYI(华羿微)"))
      (libsource (lib "easyedapro") (part "HYG110P04LQ2C2"))
    )
    (comp (ref "Q4")
      (value "MMBT3904T")
      (footprint "easyedapro:SOT-523-3_L1.6-W0.8-P1.00-LS1.6-BR")
      (description "晶体管类型:NPN;集电极电流(Ic):200mA;集射极击穿电压(Vceo):40V;功率(Pd):250mW;")
      (fields (field (name "Manufacturer") "CJ(江苏长电/长晶)"))
      (libsource (lib "easyedapro") (part "MMBT3904T"))
    )
    (comp (ref "Q5")
      (value "MMBT3904T")
      (footprint "easyedapro:SOT-523-3_L1.6-W0.8-P1.00-LS1.6-BR")
      (description "晶体管类型:NPN;集电极电流(Ic):200mA;集射极击穿电压(Vceo):40V;功率(Pd):250mW;")
      (fields (field (name "Manufacturer") "CJ(江苏长电/长晶)"))
      (libsource (lib "easyedapro") (part "MMBT3904T"))
    )
    (comp (ref "Q6")
      (value "HYG110P04LQ2C2")
      (footprint "easyedapro:PDFN-8_L5.2-W5.9-P1.27-LS6.2-BL")
      (fields (field (name "Manufacturer") "HUAYI(华羿微)"))
      (libsource (lib "easyedapro") (part "HYG110P04LQ2C2"))
    )
    (comp (ref "Q7")
      (value "HYG110P04LQ2C2")
      (footprint "easyedapro:PDFN-8_L5.2-W5.9-P1.27-LS6.2-BL")
      (fields (field (name "Manufacturer") "HUAYI(华羿微)"))
      (libsource (lib "easyedapro") (part "HYG110P04LQ2C2"))
    )
    (comp (ref "Q8")
      (value "MMBT3904T")
      (footprint "easyedapro:SOT-523-3_L1.6-W0.8-P1.00-LS1.6-BR")
      (description "晶体管类型:NPN;集电极电流(Ic):200mA;集射极击穿电压(Vceo):40V;功率(Pd):250mW;")
      (fields (field (name "Manufacturer") "CJ(江苏长电/长晶)"))
      (libsource (lib "easyedapro") (part "MMBT3904T"))
    )
    (comp (ref "Q9")
      (value "MMBT3904T")
      (footprint "easyedapro:SOT-523-3_L1.6-W0.8-P1.00-LS1.6-BR")
      (description "晶体管类型:NPN;集电极电流(Ic):200mA;集射极击穿电压(Vceo):40V;功率(Pd):250mW;")
      (fields (field (name "Manufacturer") "CJ(江苏长电/长晶)"))
      (libsource (lib "easyedapro") (part "MMBT3904T"))
    )
    (comp (ref "Q10")
      (value "HYG110P04LQ2C2")
      (footprint "easyedapro:PDFN-8_L5.2-W5.9-P1.27-LS6.2-BL")
      (fields (field (name "Manufacturer") "HUAYI(华羿微)"))
      (libsource (lib "easyedapro") (part "HYG110P04LQ2C2"))
    )
    (comp (ref "Q11")
      (value "HYG110P04LQ2C2")
      (footprint "easyedapro:PDFN-8_L5.2-W5.9-P1.27-LS6.2-BL")
      (fields (field (name "Manufacturer") "HUAYI(华羿微)"))
      (libsource (lib "easyedapro") (part "HYG110P04LQ2C2"))
    )
    (comp (ref "Q12")
      (value "MMBT3904T")
      (footprint "easyedapro:SOT-523-3_L1.6-W0.8-P1.00-LS1.6-BR")
      (description "晶体管类型:NPN;集电极电流(Ic):200mA;集射极击穿电压(Vceo):40V;功率(Pd):250mW;")
      (fields (field (name "Manufacturer") "CJ(江苏长电/长晶)"))
      (libsource (lib "easyedapro") (part "MMBT3904T"))
    )
    (comp (ref "Q13")
      (value "MMBT3904T")
      (footprint "easyedapro:SOT-523-3_L1.6-W0.8-P1.00-LS1.6-BR")
      (description "晶体管类型:NPN;集电极电流(Ic):200mA;集射极击穿电压(Vceo):40V;功率(Pd):250mW;")
      (fields (field (name "Manufacturer") "CJ(江苏长电/长晶)"))
      (libsource (lib "easyedapro") (part "MMBT3904T"))
    )
    (comp (ref "Q14")
      (value "HYG110P04LQ2C2")
      (footprint "easyedapro:PDFN-8_L5.2-W5.9-P1.27-LS6.2-BL")
      (fields (field (name "Manufacturer") "HUAYI(华羿微)"))
      (libsource (lib "easyedapro") (part "HYG110P04LQ2C2"))
    )
    (comp (ref "Q15")
      (value "HYG110P04LQ2C2")
      (footprint "easyedapro:PDFN-8_L5.2-W5.9-P1.27-LS6.2-BL")
      (fields (field (name "Manufacturer") "HUAYI(华羿微)"))
      (libsource (lib "easyedapro") (part "HYG110P04LQ2C2"))
    )
    (comp (ref "Q16")
      (value "MMBT3904T")
      (footprint "easyedapro:SOT-523-3_L1.6-W0.8-P1.00-LS1.6-BR")
      (description "晶体管类型:NPN;集电极电流(Ic):200mA;集射极击穿电压(Vceo):40V;功率(Pd):250mW;")
      (fields (field (name "Manufacturer") "CJ(江苏长电/长晶)"))
      (libsource (lib "easyedapro") (part "MMBT3904T"))
    )
    (comp (ref "Q17")
      (value "MMBT3904T")
      (footprint "easyedapro:SOT-523-3_L1.6-W0.8-P1.00-LS1.6-BR")
      (description "晶体管类型:NPN;集电极电流(Ic):200mA;集射极击穿电压(Vceo):40V;功率(Pd):250mW;")
      (fields (field (name "Manufacturer") "CJ(江苏长电/长晶)"))
      (libsource (lib "easyedapro") (part "MMBT3904T"))
    )
    (comp (ref "R1")
      (value "100k")
      (footprint "easyedapro:R0402")
      (description "电阻类型:厚膜电阻;阻值:100kΩ;精度:±1%;功率:62.5mW;最大工作电压:50V;温度系数:±100ppm/°C;")
      (fields
        (field (name "Manufacturer Part") "0402WGF1003TCE")
        (field (name "Manufacturer") "UNI-ROYAL(厚声)")
      )
      (libsource (lib "easyedapro") (part "0402WGF1003TCE"))
    )
    (comp (ref "R2")
      (value "10kΩ")
      (footprint "easyedapro:R0402")
      (description "电阻类型:厚膜电阻;阻值:10kΩ;精度:±1%;功率:62.5mW;最大工作电压:50V;温度系数:±100ppm/°C;")
      (fields
        (field (name "Manufacturer Part") "0402WGF1002TCE")
        (field (name "Manufacturer") "UNI-ROYAL(厚声)")
      )
      (libsource (lib "easyedapro") (part "0402WGF1002TCE"))
    )
    (comp (ref "R3")
      (value "8.2k")
      (footprint "easyedapro:R0402")
      (description "电阻类型:厚膜电阻;阻值:8.2kΩ;精度:±1%;功率:62.5mW;最大工作电压:50V;温度系数:±100ppm/°C;")
      (fields
        (field (name "Manufacturer Part") "0402WGF8201TCE")
        (field (name "Manufacturer") "UNI-ROYAL(厚声)")
      )
      (libsource (lib "easyedapro") (part "0402WGF8201TCE"))
    )
    (comp (ref "R4")
      (value "100kΩ")
      (footprint "easyedapro:R0402")
      (description "电阻类型:厚膜电阻;阻值:100kΩ;精度:±1%;功率:62.5mW;最大工作电压:50V;温度系数:±100ppm/°C;")
      (fields
        (field (name "Manufacturer Part") "0402WGF1003TCE")
        (field (name "Manufacturer") "UNI-ROYAL(厚声)")
      )
      (libsource (lib "easyedapro") (part "0402WGF1003TCE"))
    )
    (comp (ref "R5")
      (value "100kΩ")
      (footprint "easyedapro:R0402")
      (description "电阻类型:厚膜电阻;阻值:100kΩ;精度:±1%;功率:62.5mW;最大工作电压:50V;温度系数:±100ppm/°C;")
      (fields
        (field (name "Manufacturer Part") "0402WGF1003TCE")
        (field (name "Manufacturer") "UNI-ROYAL(厚声)")
      )
      (libsource (lib "easyedapro") (part "0402WGF1003TCE"))
    )
    (comp (ref "R6")
      (value "100kΩ")
      (footprint "easyedapro:R0402")
      (description "电阻类型:厚膜电阻;阻值:100kΩ;精度:±1%;功率:62.5mW;最大工作电压:50V;温度系数:±100ppm/°C;")
      (fields
        (field (name "Manufacturer Part") "0402WGF1003TCE")
        (field (name "Manufacturer") "UNI-ROYAL(厚声)")
      )
      (libsource (lib "easyedapro") (part "0402WGF1003TCE"))
    )
    (comp (ref "R7")
      (value "44.2kΩ")
      (footprint "easyedapro:R0402")
      (description "电阻类型:厚膜电阻;阻值:44.2kΩ;精度:±1%;功率:62.5mW;工作电压:50V;温度系数:±100ppm/°C;")
      (fields (field (name "Manufacturer Part") "FRC0402F4422TS") (field (name "Manufacturer") "FOJAN(富捷)"))
      (libsource (lib "easyedapro") (part "FRC0402F4422TS"))
    )
    (comp (ref "R8")
      (value "10kΩ")
      (footprint "easyedapro:R0402")
      (description "电阻类型:厚膜电阻;阻值:10kΩ;精度:±1%;功率:62.5mW;最大工作电压:50V;温度系数:±100ppm/°C;")
      (fields
        (field (name "Manufacturer Part") "0402WGF1002TCE")
        (field (name "Manufacturer") "UNI-ROYAL(厚声)")
      )
      (libsource (lib "easyedapro") (part "0402WGF1002TCE"))
    )
    (comp (ref "R9")
      (value "0Ω")
      (footprint "easyedapro:R0402")
      (description "电阻类型:厚膜电阻;阻值:0Ω;精度:±1%;功率:62.5mW;最大工作电压:50V;温度系数:±800ppm/°C;")
      (fields
        (field (name "Manufacturer Part") "0402WGF0000TCE")
        (field (name "Manufacturer") "UNI-ROYAL(厚声)")
      )
      (libsource (lib "easyedapro") (part "0402WGF0000TCE"))
    )
    (comp (ref "R10")
      (value "5kΩ")
      (footprint "easyedapro:R0402")
      (description "电阻类型:厚膜电阻;阻值:5kΩ;精度:±1%;功率:62.5mW;最大工作电压:50V;温度系数:±100ppm/°C;")
      (fields (field (name "Manufacturer Part") "RC0402FR-075KL") (field (name "Manufacturer") "YAGEO(国巨)"))
      (libsource (lib "easyedapro") (part "RC0402FR-075KL"))
    )
    (comp (ref "R11")
      (value "5kΩ")
      (footprint "easyedapro:R0402")
      (description "电阻类型:厚膜电阻;阻值:5kΩ;精度:±1%;功率:62.5mW;最大工作电压:50V;温度系数:±100ppm/°C;")
      (fields (field (name "Manufacturer Part") "RC0402FR-075KL") (field (name "Manufacturer") "YAGEO(国巨)"))
      (libsource (lib "easyedapro") (part "RC0402FR-075KL"))
    )
    (comp (ref "R12")
      (value "1kΩ")
      (footprint "easyedapro:R0402")
      (description "电阻类型:薄膜电阻;阻值:1kΩ;精度:±0.1%;功率:62.5mW;最大工作电压:50V;温度系数:±25ppm/°C;")
      (fields (field (name "Manufacturer Part") "RT0402BRD071KL") (field (name "Manufacturer") "YAGEO(国巨)"))
      (libsource (lib "easyedapro") (part "RT0402BRD071KL"))
    )
    (comp (ref "R13")
      (value "1kΩ")
      (footprint "easyedapro:R0402")
      (description "电阻类型:薄膜电阻;阻值:1kΩ;精度:±0.1%;功率:62.5mW;最大工作电压:50V;温度系数:±25ppm/°C;")
      (fields (field (name "Manufacturer Part") "RT0402BRD071KL") (field (name "Manufacturer") "YAGEO(国巨)"))
      (libsource (lib "easyedapro") (part "RT0402BRD071KL"))
    )
    (comp (ref "R14")
      (value "10kΩ")
      (footprint "easyedapro:R0402")
      (description "电阻类型:厚膜电阻;阻值:10kΩ;精度:±1%;功率:62.5mW;最大工作电压:50V;温度系数:±100ppm/°C;")
      (fields
        (field (name "Manufacturer Part") "0402WGF1002TCE")
        (field (name "Manufacturer") "UNI-ROYAL(厚声)")
      )
      (libsource (lib "easyedapro") (part "0402WGF1002TCE"))
    )
    (comp (ref "R15")
      (value "10kΩ")
      (footprint "easyedapro:R0402")
      (description "电阻类型:厚膜电阻;阻值:10kΩ;精度:±1%;功率:62.5mW;最大工作电压:50V;温度系数:±100ppm/°C;")
      (fields
        (field (name "Manufacturer Part") "0402WGF1002TCE")
        (field (name "Manufacturer") "UNI-ROYAL(厚声)")
      )
      (libsource (lib "easyedapro") (part "0402WGF1002TCE"))
    )
    (comp (ref "R16")
      (value "10kΩ")
      (footprint "easyedapro:R0402")
      (description "电阻类型:厚膜电阻;阻值:10kΩ;精度:±1%;功率:62.5mW;最大工作电压:50V;温度系数:±100ppm/°C;")
      (fields
        (field (name "Manufacturer Part") "0402WGF1002TCE")
        (field (name "Manufacturer") "UNI-ROYAL(厚声)")
      )
      (libsource (lib "easyedapro") (part "0402WGF1002TCE"))
    )
    (comp (ref "R17")
      (value "10kΩ")
      (footprint "easyedapro:R0402")
      (description "电阻类型:厚膜电阻;阻值:10kΩ;精度:±1%;功率:62.5mW;最大工作电压:50V;温度系数:±100ppm/°C;")
      (fields
        (field (name "Manufacturer Part") "0402WGF1002TCE")
        (field (name "Manufacturer") "UNI-ROYAL(厚声)")
      )
      (libsource (lib "easyedapro") (part "0402WGF1002TCE"))
    )
    (comp (ref "R18")
      (value "10kΩ")
      (footprint "easyedapro:R0402")
      (description "电阻类型:厚膜电阻;阻值:10kΩ;精度:±1%;功率:62.5mW;最大工作电压:50V;温度系数:±100ppm/°C;")
      (fields
        (field (name "Manufacturer Part") "0402WGF1002TCE")
        (field (name "Manufacturer") "UNI-ROYAL(厚声)")
      )
      (libsource (lib "easyedapro") (part "0402WGF1002TCE"))
    )
    (comp (ref "R19")
      (value "10kΩ")
      (footprint "easyedapro:R0402")
      (description "电阻类型:厚膜电阻;阻值:10kΩ;精度:±1%;功率:62.5mW;最大工作电压:50V;温度系数:±100ppm/°C;")
      (fields
        (field (name "Manufacturer Part") "0402WGF1002TCE")
        (field (name "Manufacturer") "UNI-ROYAL(厚声)")
      )
      (libsource (lib "easyedapro") (part "0402WGF1002TCE"))
    )
    (comp (ref "R20")
      (value "1kΩ")
      (footprint "easyedapro:R0402")
      (description "电阻类型:薄膜电阻;阻值:1kΩ;精度:±0.1%;功率:62.5mW;最大工作电压:50V;温度系数:±25ppm/°C;")
      (fields (field (name "Manufacturer Part") "RT0402BRD071KL") (field (name "Manufacturer") "YAGEO(国巨)"))
      (libsource (lib "easyedapro") (part "RT0402BRD071KL"))
    )
    (comp (ref "R21")
      (value "1kΩ")
      (footprint "easyedapro:R0402")
      (description "电阻类型:薄膜电阻;阻值:1kΩ;精度:±0.1%;功率:62.5mW;最大工作电压:50V;温度系数:±25ppm/°C;")
      (fields (field (name "Manufacturer Part") "RT0402BRD071KL") (field (name "Manufacturer") "YAGEO(国巨)"))
      (libsource (lib "easyedapro") (part "RT0402BRD071KL"))
    )
    (comp (ref "R22")
      (value "10kΩ")
      (footprint "easyedapro:R0402")
      (description "电阻类型:厚膜电阻;阻值:10kΩ;精度:±1%;功率:62.5mW;最大工作电压:50V;温度系数:±100ppm/°C;")
      (fields
        (field (name "Manufacturer Part") "0402WGF1002TCE")
        (field (name "Manufacturer") "UNI-ROYAL(厚声)")
      )
      (libsource (lib "easyedapro") (part "0402WGF1002TCE"))
    )
    (comp (ref "R23")
      (value "10kΩ")
      (footprint "easyedapro:R0402")
      (description "电阻类型:厚膜电阻;阻值:10kΩ;精度:±1%;功率:62.5mW;最大工作电压:50V;温度系数:±100ppm/°C;")
      (fields
        (field (name "Manufacturer Part") "0402WGF1002TCE")
        (field (name "Manufacturer") "UNI-ROYAL(厚声)")
      )
      (libsource (lib "easyedapro") (part "0402WGF1002TCE"))
    )
    (comp (ref "R24")
      (value "10kΩ")
      (footprint "easyedapro:R0402")
      (description "电阻类型:厚膜电阻;阻值:10kΩ;精度:±1%;功率:62.5mW;最大工作电压:50V;温度系数:±100ppm/°C;")
      (fields
        (field (name "Manufacturer Part") "0402WGF1002TCE")
        (field (name "Manufacturer") "UNI-ROYAL(厚声)")
      )
      (libsource (lib "easyedapro") (part "0402WGF1002TCE"))
    )
    (comp (ref "R25")
      (value "10kΩ")
      (footprint "easyedapro:R0402")
      (description "电阻类型:厚膜电阻;阻值:10kΩ;精度:±1%;功率:62.5mW;最大工作电压:50V;温度系数:±100ppm/°C;")
      (fields
        (field (name "Manufacturer Part") "0402WGF1002TCE")
        (field (name "Manufacturer") "UNI-ROYAL(厚声)")
      )
      (libsource (lib "easyedapro") (part "0402WGF1002TCE"))
    )
    (comp (ref "R26")
      (value "10kΩ")
      (footprint "easyedapro:R0402")
      (description "电阻类型:厚膜电阻;阻值:10kΩ;精度:±1%;功率:62.5mW;最大工作电压:50V;温度系数:±100ppm/°C;")
      (fields
        (field (name "Manufacturer Part") "0402WGF1002TCE")
        (field (name "Manufacturer") "UNI-ROYAL(厚声)")
      )
      (libsource (lib "easyedapro") (part "0402WGF1002TCE"))
    )
    (comp (ref "R27")
      (value "10kΩ")
      (footprint "easyedapro:R0402")
      (description "电阻类型:厚膜电阻;阻值:10kΩ;精度:±1%;功率:62.5mW;最大工作电压:50V;温度系数:±100ppm/°C;")
      (fields
        (field (name "Manufacturer Part") "0402WGF1002TCE")
        (field (name "Manufacturer") "UNI-ROYAL(厚声)")
      )
      (libsource (lib "easyedapro") (part "0402WGF1002TCE"))
    )
    (comp (ref "R28")
      (value "1kΩ")
      (footprint "easyedapro:R0402")
      (description "电阻类型:薄膜电阻;阻值:1kΩ;精度:±0.1%;功率:62.5mW;最大工作电压:50V;温度系数:±25ppm/°C;")
      (fields (field (name "Manufacturer Part") "RT0402BRD071KL") (field (name "Manufacturer") "YAGEO(国巨)"))
      (libsource (lib "easyedapro") (part "RT0402BRD071KL"))
    )
    (comp (ref "R29")
      (value "1kΩ")
      (footprint "easyedapro:R0402")
      (description "电阻类型:薄膜电阻;阻值:1kΩ;精度:±0.1%;功率:62.5mW;最大工作电压:50V;温度系数:±25ppm/°C;")
      (fields (field (name "Manufacturer Part") "RT0402BRD071KL") (field (name "Manufacturer") "YAGEO(国巨)"))
      (libsource (lib "easyedapro") (part "RT0402BRD071KL"))
    )
    (comp (ref "R30")
      (value "10kΩ")
      (footprint "easyedapro:R0402")
      (description "电阻类型:厚膜电阻;阻值:10kΩ;精度:±1%;功率:62.5mW;最大工作电压:50V;温度系数:±100ppm/°C;")
      (fields
        (field (name "Manufacturer Part") "0402WGF1002TCE")
        (field (name "Manufacturer") "UNI-ROYAL(厚声)")
      )
      (libsource (lib "easyedapro") (part "0402WGF1002TCE"))
    )
    (comp (ref "R31")
      (value "10kΩ")
      (footprint "easyedapro:R0402")
      (description "电阻类型:厚膜电阻;阻值:10kΩ;精度:±1%;功率:62.5mW;最大工作电压:50V;温度系数:±100ppm/°C;")
      (fields
        (field (name "Manufacturer Part") "0402WGF1002TCE")
        (field (name "Manufacturer") "UNI-ROYAL(厚声)")
      )
      (libsource (lib "easyedapro") (part "0402WGF1002TCE"))
    )
    (comp (ref "R32")
      (value "10kΩ")
      (footprint "easyedapro:R0402")
      (description "电阻类型:厚膜电阻;阻值:10kΩ;精度:±1%;功率:62.5mW;最大工作电压:50V;温度系数:±100ppm/°C;")
      (fields
        (field (name "Manufacturer Part") "0402WGF1002TCE")
        (field (name "Manufacturer") "UNI-ROYAL(厚声)")
      )
      (libsource (lib "easyedapro") (part "0402WGF1002TCE"))
    )
    (comp (ref "R33")
      (value "10kΩ")
      (footprint "easyedapro:R0402")
      (description "电阻类型:厚膜电阻;阻值:10kΩ;精度:±1%;功率:62.5mW;最大工作电压:50V;温度系数:±100ppm/°C;")
      (fields
        (field (name "Manufacturer Part") "0402WGF1002TCE")
        (field (name "Manufacturer") "UNI-ROYAL(厚声)")
      )
      (libsource (lib "easyedapro") (part "0402WGF1002TCE"))
    )
    (comp (ref "R34")
      (value "10kΩ")
      (footprint "easyedapro:R0402")
      (description "电阻类型:厚膜电阻;阻值:10kΩ;精度:±1%;功率:62.5mW;最大工作电压:50V;温度系数:±100ppm/°C;")
      (fields
        (field (name "Manufacturer Part") "0402WGF1002TCE")
        (field (name "Manufacturer") "UNI-ROYAL(厚声)")
      )
      (libsource (lib "easyedapro") (part "0402WGF1002TCE"))
    )
    (comp (ref "R35")
      (value "10kΩ")
      (footprint "easyedapro:R0402")
      (description "电阻类型:厚膜电阻;阻值:10kΩ;精度:±1%;功率:62.5mW;最大工作电压:50V;温度系数:±100ppm/°C;")
      (fields
        (field (name "Manufacturer Part") "0402WGF1002TCE")
        (field (name "Manufacturer") "UNI-ROYAL(厚声)")
      )
      (libsource (lib "easyedapro") (part "0402WGF1002TCE"))
    )
    (comp (ref "R36")
      (value "1kΩ")
      (footprint "easyedapro:R0402")
      (description "电阻类型:薄膜电阻;阻值:1kΩ;精度:±0.1%;功率:62.5mW;最大工作电压:50V;温度系数:±25ppm/°C;")
      (fields (field (name "Manufacturer Part") "RT0402BRD071KL") (field (name "Manufacturer") "YAGEO(国巨)"))
      (libsource (lib "easyedapro") (part "RT0402BRD071KL"))
    )
    (comp (ref "R37")
      (value "1kΩ")
      (footprint "easyedapro:R0402")
      (description "电阻类型:薄膜电阻;阻值:1kΩ;精度:±0.1%;功率:62.5mW;最大工作电压:50V;温度系数:±25ppm/°C;")
      (fields (field (name "Manufacturer Part") "RT0402BRD071KL") (field (name "Manufacturer") "YAGEO(国巨)"))
      (libsource (lib "easyedapro") (part "RT0402BRD071KL"))
    )
    (comp (ref "R38")
      (value "1kΩ")
      (footprint "easyedapro:R0402")
      (description "电阻类型:薄膜电阻;阻值:1kΩ;精度:±0.1%;功率:62.5mW;最大工作电压:50V;温度系数:±25ppm/°C;")
      (fields (field (name "Manufacturer Part") "RT0402BRD071KL") (field (name "Manufacturer") "YAGEO(国巨)"))
      (libsource (lib "easyedapro") (part "RT0402BRD071KL"))
    )
    (comp (ref "R39")
      (value "1kΩ")
      (footprint "easyedapro:R0402")
      (description "电阻类型:薄膜电阻;阻值:1kΩ;精度:±0.1%;功率:62.5mW;最大工作电压:50V;温度系数:±25ppm/°C;")
      (fields (field (name "Manufacturer Part") "RT0402BRD071KL") (field (name "Manufacturer") "YAGEO(国巨)"))
      (libsource (lib "easyedapro") (part "RT0402BRD071KL"))
    )
    (comp (ref "R40")
      (value "1kΩ")
      (footprint "easyedapro:R0402")
      (description "电阻类型:薄膜电阻;阻值:1kΩ;精度:±0.1%;功率:62.5mW;最大工作电压:50V;温度系数:±25ppm/°C;")
      (fields (field (name "Manufacturer Part") "RT0402BRD071KL") (field (name "Manufacturer") "YAGEO(国巨)"))
      (libsource (lib "easyedapro") (part "RT0402BRD071KL"))
    )
    (comp (ref "R41")
      (value "10kΩ")
      (footprint "easyedapro:R0402")
      (description "电阻类型:厚膜电阻;阻值:10kΩ;精度:±1%;功率:62.5mW;最大工作电压:50V;温度系数:±100ppm/°C;")
      (fields
        (field (name "Manufacturer Part") "0402WGF1002TCE")
        (field (name "Manufacturer") "UNI-ROYAL(厚声)")
      )
      (libsource (lib "easyedapro") (part "0402WGF1002TCE"))
    )
    (comp (ref "R42")
      (value "10kΩ")
      (footprint "easyedapro:R0402")
      (description "电阻类型:厚膜电阻;阻值:10kΩ;精度:±1%;功率:62.5mW;最大工作电压:50V;温度系数:±100ppm/°C;")
      (fields
        (field (name "Manufacturer Part") "0402WGF1002TCE")
        (field (name "Manufacturer") "UNI-ROYAL(厚声)")
      )
      (libsource (lib "easyedapro") (part "0402WGF1002TCE"))
    )
    (comp (ref "R43")
      (value "10kΩ")
      (footprint "easyedapro:R0402")
      (description "电阻类型:厚膜电阻;阻值:10kΩ;精度:±1%;功率:62.5mW;最大工作电压:50V;温度系数:±100ppm/°C;")
      (fields
        (field (name "Manufacturer Part") "0402WGF1002TCE")
        (field (name "Manufacturer") "UNI-ROYAL(厚声)")
      )
      (libsource (lib "easyedapro") (part "0402WGF1002TCE"))
    )
    (comp (ref "R44")
      (value "10kΩ")
      (footprint "easyedapro:R0402")
      (description "电阻类型:厚膜电阻;阻值:10kΩ;精度:±1%;功率:62.5mW;最大工作电压:50V;温度系数:±100ppm/°C;")
      (fields
        (field (name "Manufacturer Part") "0402WGF1002TCE")
        (field (name "Manufacturer") "UNI-ROYAL(厚声)")
      )
      (libsource (lib "easyedapro") (part "0402WGF1002TCE"))
    )
    (comp (ref "R45")
      (value "10kΩ")
      (footprint "easyedapro:R0402")
      (description "电阻类型:厚膜电阻;阻值:10kΩ;精度:±1%;功率:62.5mW;最大工作电压:50V;温度系数:±100ppm/°C;")
      (fields
        (field (name "Manufacturer Part") "0402WGF1002TCE")
        (field (name "Manufacturer") "UNI-ROYAL(厚声)")
      )
      (libsource (lib "easyedapro") (part "0402WGF1002TCE"))
    )
    (comp (ref "R46")
      (value "10kΩ")
      (footprint "easyedapro:R0402")
      (description "电阻类型:厚膜电阻;阻值:10kΩ;精度:±1%;功率:62.5mW;最大工作电压:50V;温度系数:±100ppm/°C;")
      (fields
        (field (name "Manufacturer Part") "0402WGF1002TCE")
        (field (name "Manufacturer") "UNI-ROYAL(厚声)")
      )
      (libsource (lib "easyedapro") (part "0402WGF1002TCE"))
    )
    (comp (ref "RN1")
      (value "1kΩ")
      (footprint "easyedapro:RES-ARRAY-SMD_0603-8P-L3.2-W1.6-BL")
      (description "电阻器数:4;阻值:1kΩ;精度:±5%;单个元件功率:62.5mW;温度系数:±100ppm/°C;")
      (fields (field (name "Manufacturer Part") "RC-ML08W102JT") (field (name "Manufacturer") "FH(风华)"))
      (libsource (lib "easyedapro") (part "RC-ML08W102JT"))
    )
    (comp (ref "RN2")
      (value "1kΩ")
      (footprint "easyedapro:RES-ARRAY-SMD_0603-8P-L3.2-W1.6-BL")
      (description "电阻器数:4;阻值:1kΩ;精度:±5%;单个元件功率:62.5mW;温度系数:±100ppm/°C;")
      (fields (field (name "Manufacturer Part") "RC-ML08W102JT") (field (name "Manufacturer") "FH(风华)"))
      (libsource (lib "easyedapro") (part "RC-ML08W102JT"))
    )
    (comp (ref "RXD")
      (value "NCD0402G1")
      (footprint "easyedapro:LED0402-RD")
      (fields (field (name "Manufacturer") "国星光电"))
      (libsource (lib "easyedapro") (part "FC-F1005UGK-520M5"))
    )
    (comp (ref "SW1")
      (value "K3-1391D-5MM")
      (footprint "easyedapro:SW-TH_K3-1391D-5MM")
      (description "电路结构:单刀双掷;安装方式:直插;开关颜色:黑色;额定电流(DC):-;额定电压(DC):-;额定电流(AC):3A;额定电压(AC):120V;机械寿命:3万次;")
      (fields (field (name "Manufacturer") "韩国韩荣"))
      (libsource (lib "easyedapro") (part "K3-1391D-5MM"))
    )
    (comp (ref "TXD")
      (value "NCD0402G1")
      (footprint "easyedapro:LED0402-RD")
      (fields (field (name "Manufacturer") "国星光电"))
      (libsource (lib "easyedapro") (part "FC-F1005UGK-520M5"))
    )
    (comp (ref "U1")
      (value "PCA9685PW,118")
      (footprint "easyedapro:TSSOP-28_L9.7-W4.4-P0.65-LS6.4-TL")
      (description "类型:-;输入电压:2.3V~5.5V;开关频率:100kHz~1MHz;通道数:16;输出电压:5.5V;输出电流:25mA;调光:PWM;")
      (fields (field (name "Manufacturer") "NXP(恩智浦)"))
      (libsource (lib "easyedapro") (part "PCA9685PW,118"))
    )
    (comp (ref "U2")
      (value "MP1584EN-LF-P")
      (footprint "easyedapro:SOIC-8_L4.9-W3.9-P1.27-LS6.0-TL-EP-1")
      (description "功能类型:降压型;输出类型:可调;工作电压:4.5V~28V;输出电压:800mV~25V;输出电流:3A;")
      (fields (field (name "Manufacturer") "MPS(芯源)"))
      (libsource (lib "easyedapro") (part "MP1584EN-LF-P"))
    )
    (comp (ref "U3")
      (value "AMS1117-3.3")
      (footprint "easyedapro:SOT-223-3_L6.5-W3.4-P2.30-LS7.0-BR")
      (description "输出类型:固定;最大输入电压:-;输出电压:3.3V;最大输出电流:1A;电源纹波抑制比(PSRR):72dB@(120Hz);输出极性:正极;")
      (fields (field (name "Manufacturer") "AMS"))
      (libsource (lib "easyedapro") (part "AMS1117-3.3"))
    )
    (comp (ref "U4")
      (value "PCA9685PW,118")
      (footprint "easyedapro:TSSOP-28_L9.7-W4.4-P0.65-LS6.4-TL")
      (description "类型:-;输入电压:2.3V~5.5V;开关频率:100kHz~1MHz;通道数:16;输出电压:5.5V;输出电流:25mA;调光:PWM;")
      (fields (field (name "Manufacturer") "NXP(恩智浦)"))
      (libsource (lib "easyedapro") (part "PCA9685PW,118"))
    )
    (comp (ref "U5")
      (value "CH340C")
      (footprint "easyedapro:SOP-16_L10.0-W3.9-P1.27-LS6.0-BL")
      (description "应用功能:收发器;接口协议:USB 2.0;数据速率:2Mbps;")
      (fields (field (name "Manufacturer") "WCH(南京沁恒)"))
      (libsource (lib "easyedapro") (part "CH340C"))
    )
    (comp (ref "U6")
      (value "ESP32-WROOM-32E-N8")
      (footprint "easyedapro:WIFI-SMD_ESP32-WROOM-32E")
      (description "ESP32-WROOM-32E 集成 ESP32-D0WD-V3 芯片，具有?高的稳定性和安全性能。")
      (fields (field (name "Manufacturer") "ESPRESSIF(乐鑫)"))
      (libsource (lib "easyedapro") (part "ESP32-WROOM-32E(8MB)"))
    )
    (comp (ref "U7")
      (value "MPU-6050")
      (footprint "easyedapro:QFN-24_L4.0-W4.0-P0.50-BL-EP2.7")
      (description "传感器类型:加速度计陀螺仪;")
      (fields (field (name "Manufacturer") "TDK InvenSense(应美盛)"))
      (libsource (lib "easyedapro") (part "MPU-6050_C24112"))
    )
    (comp (ref "USB1")
      (value "TYPE-C16PIN")
      (footprint "easyedapro:USB-C-SMD_TYPE-C16PIN")
      (description "连接器类型:Type-C;标准:USB 3.1;公母:母;安装方式:卧贴;触点数量:16P;端口数量:1;额定电流 - 电源:3A;工作温度范围:-40°C~+85°C;")
      (fields (field (name "Manufacturer") "SHOU HAN(首韩)"))
      (libsource (lib "easyedapro") (part "TYPE-C16PIN"))
    )
  )
  (nets
    (net (code "1") (name "/BOOT") (class "Default")
      (node (ref "BOOT") (pin "1") (pinfunction "K_1") (pintype "unspecified"))
      (node (ref "BOOT1") (pin "1") (pinfunction "1_1") (pintype "unspecified"))
      (node (ref "C33") (pin "2") (pinfunction "2_2") (pintype "unspecified"))
      (node (ref "Q1") (pin "3") (pinfunction "C_3") (pintype "unspecified"))
      (node (ref "R36") (pin "2") (pinfunction "2_2") (pintype "unspecified"))
      (node (ref "U6") (pin "25") (pinfunction "IO0_25") (pintype "unspecified"))
    )
    (net (code "2") (name "/D+") (class "Default")
      (node (ref "U5") (pin "5") (pinfunction "D+_5") (pintype "unspecified"))
      (node (ref "USB1") (pin "A6") (pinfunction "DP1_A6") (pintype "unspecified"))
      (node (ref "USB1") (pin "B6") (pinfunction "DP2_B6") (pintype "unspecified"))
    )
    (net (code "3") (name "/D-") (class "Default")
      (node (ref "U5") (pin "6") (pinfunction "D-_6") (pintype "unspecified"))
      (node (ref "USB1") (pin "A7") (pinfunction "DN1_A7") (pintype "unspecified"))
      (node (ref "USB1") (pin "B7") (pinfunction "DN2_B7") (pintype "unspecified"))
    )
    (net (code "4") (name "/DTR") (class "Default")
      (node (ref "Q1") (pin "2") (pinfunction "B_2") (pintype "unspecified"))
      (node (ref "Q1") (pin "4") (pinfunction "E_4") (pintype "unspecified"))
      (node (ref "U5") (pin "13") (pinfunction "DTR#_13") (pintype "unspecified"))
    )
    (net (code "5") (name "/EN") (class "Default")
      (node (ref "C36") (pin "2") (pinfunction "2_2") (pintype "unspecified"))
      (node (ref "EN") (pin "1") (pinfunction "1_1") (pintype "unspecified"))
      (node (ref "Q1") (pin "6") (pinfunction "C_6") (pintype "unspecified"))
      (node (ref "R40") (pin "2") (pinfunction "2_2") (pintype "unspecified"))
      (node (ref "U6") (pin "3") (pinfunction "EN_3") (pintype "unspecified"))
    )
    (net (code "6") (name "/IO4") (class "Default")
      (node (ref "RN2") (pin "3") (pinfunction "3_3") (pintype "input"))
      (node (ref "RN2") (pin "4") (pinfunction "4_4") (pintype "input"))
      (node (ref "U6") (pin "10") (pinfunction "IO25_10") (pintype "unspecified"))
    )
    (net (code "7") (name "/IO25") (class "Default")
      (node (ref "C29") (pin "2") (pinfunction "2_2") (pintype "unspecified"))
      (node (ref "R29") (pin "2") (pinfunction "2_2") (pintype "unspecified"))
      (node (ref "U6") (pin "28") (pinfunction "IO17_28") (pintype "unspecified"))
    )
    (net (code "8") (name "/IO26") (class "Default")
      (node (ref "C35") (pin "2") (pinfunction "2_2") (pintype "unspecified"))
      (node (ref "R39") (pin "2") (pinfunction "2_2") (pintype "unspecified"))
      (node (ref "U6") (pin "11") (pinfunction "IO26_11") (pintype "unspecified"))
    )
    (net (code "9") (name "/IO32") (class "Default")
      (node (ref "C17") (pin "2") (pinfunction "2_2") (pintype "unspecified"))
      (node (ref "R13") (pin "2") (pinfunction "2_2") (pintype "unspecified"))
      (node (ref "U6") (pin "30") (pinfunction "IO18_30") (pintype "unspecified"))
    )
    (net (code "10") (name "/IO33") (class "Default")
      (node (ref "C21") (pin "2") (pinfunction "2_2") (pintype "unspecified"))
      (node (ref "R21") (pin "2") (pinfunction "2_2") (pintype "unspecified"))
      (node (ref "U6") (pin "31") (pinfunction "IO19_31") (pintype "unspecified"))
    )
    (net (code "11") (name "/IO34") (class "Default")
      (node (ref "C28") (pin "2") (pinfunction "2_2") (pintype "unspecified"))
      (node (ref "R28") (pin "2") (pinfunction "2_2") (pintype "unspecified"))
      (node (ref "U6") (pin "12") (pinfunction "IO27_12") (pintype "unspecified"))
    )
    (net (code "12") (name "/IO35") (class "Default")
      (node (ref "C34") (pin "2") (pinfunction "2_2") (pintype "unspecified"))
      (node (ref "R38") (pin "2") (pinfunction "2_2") (pintype "unspecified"))
      (node (ref "U6") (pin "29") (pinfunction "IO5_29") (pintype "unspecified"))
    )
    (net (code "13") (name "/IO36") (class "Default")
      (node (ref "C16") (pin "2") (pinfunction "2_2") (pintype "unspecified"))
      (node (ref "R12") (pin "2") (pinfunction "2_2") (pintype "unspecified"))
      (node (ref "U6") (pin "14") (pinfunction "IO12_14") (pintype "unspecified"))
    )
    (net (code "14") (name "/IO39") (class "Default")
      (node (ref "C20") (pin "2") (pinfunction "2_2") (pintype "unspecified"))
      (node (ref "R20") (pin "2") (pinfunction "2_2") (pintype "unspecified"))
      (node (ref "U6") (pin "13") (pinfunction "IO14_13") (pintype "unspecified"))
    )
    (net (code "15") (name "/RTS") (class "Default")
      (node (ref "Q1") (pin "1") (pinfunction "E_1") (pintype "unspecified"))
      (node (ref "Q1") (pin "5") (pinfunction "B_5") (pintype "unspecified"))
      (node (ref "U5") (pin "14") (pinfunction "RTS#_14") (pintype "unspecified"))
    )
    (net (code "16") (name "/SCL") (class "Default")
      (node (ref "U1") (pin "26") (pinfunction "SCL_26") (pintype "unspecified"))
      (node (ref "U4") (pin "26") (pinfunction "SCL_26") (pintype "unspecified"))
      (node (ref "U6") (pin "36") (pinfunction "IO22_36") (pintype "unspecified"))
      (node (ref "U7") (pin "23") (pinfunction "SCL_23") (pintype "unspecified"))
    )
    (net (code "17") (name "/SDA") (class "Default")
      (node (ref "U1") (pin "27") (pinfunction "SDA_27") (pintype "unspecified"))
      (node (ref "U4") (pin "27") (pinfunction "SDA_27") (pintype "unspecified"))
      (node (ref "U6") (pin "33") (pinfunction "IO21_33") (pintype "unspecified"))
      (node (ref "U7") (pin "24") (pinfunction "SDA_24") (pintype "unspecified"))
    )
    (net (code "18") (name "/SERVO0") (class "Default")
      (node (ref "H1") (pin "1") (pinfunction "1_1") (pintype "unspecified"))
      (node (ref "U1") (pin "22") (pinfunction "LED15_22") (pintype "unspecified"))
    )
    (net (code "19") (name "/SERVO1") (class "Default")
      (node (ref "H4") (pin "1") (pinfunction "1_1") (pintype "unspecified"))
      (node (ref "U1") (pin "21") (pinfunction "LED14_21") (pintype "unspecified"))
    )
    (net (code "20") (name "/SERVO2") (class "Default")
      (node (ref "H7") (pin "1") (pinfunction "1_1") (pintype "unspecified"))
      (node (ref "U1") (pin "20") (pinfunction "LED13_20") (pintype "unspecified"))
    )
    (net (code "21") (name "/SERVO3") (class "Default")
      (node (ref "H2") (pin "1") (pinfunction "1_1") (pintype "unspecified"))
      (node (ref "U1") (pin "19") (pinfunction "LED12_19") (pintype "unspecified"))
    )
    (net (code "22") (name "/SERVO4") (class "Default")
      (node (ref "H5") (pin "1") (pinfunction "1_1") (pintype "unspecified"))
      (node (ref "U1") (pin "18") (pinfunction "LED11_18") (pintype "unspecified"))
    )
    (net (code "23") (name "/SERVO5") (class "Default")
      (node (ref "H8") (pin "1") (pinfunction "1_1") (pintype "unspecified"))
      (node (ref "U1") (pin "17") (pinfunction "LED10_17") (pintype "unspecified"))
    )
    (net (code "24") (name "/SERVO6") (class "Default")
      (node (ref "H3") (pin "1") (pinfunction "1_1") (pintype "unspecified"))
      (node (ref "U1") (pin "16") (pinfunction "LED9_16") (pintype "unspecified"))
    )
    (net (code "25") (name "/SERVO7") (class "Default")
      (node (ref "H6") (pin "1") (pinfunction "1_1") (pintype "unspecified"))
      (node (ref "U1") (pin "15") (pinfunction "LED8_15") (pintype "unspecified"))
    )
    (net (code "26") (name "/SERVO8") (class "Default")
      (node (ref "H9") (pin "1") (pinfunction "1_1") (pintype "unspecified"))
      (node (ref "U1") (pin "6") (pinfunction "LED0_6") (pintype "unspecified"))
    )
    (net (code "27") (name "/SERVO9") (class "Default")
      (node (ref "H10") (pin "1") (pinfunction "1_1") (pintype "unspecified"))
      (node (ref "U1") (pin "7") (pinfunction "LED1_7") (pintype "unspecified"))
    )
    (net (code "28") (name "/SERVO10") (class "Default")
      (node (ref "H13") (pin "1") (pinfunction "1_1") (pintype "unspecified"))
      (node (ref "U1") (pin "8") (pinfunction "LED2_8") (pintype "unspecified"))
    )
    (net (code "29") (name "/SERVO11") (class "Default")
      (node (ref "H16") (pin "1") (pinfunction "1_1") (pintype "unspecified"))
      (node (ref "U1") (pin "9") (pinfunction "LED3_9") (pintype "unspecified"))
    )
    (net (code "30") (name "/SERVO12") (class "Default")
      (node (ref "H11") (pin "1") (pinfunction "1_1") (pintype "unspecified"))
      (node (ref "U1") (pin "10") (pinfunction "LED4_10") (pintype "unspecified"))
    )
    (net (code "31") (name "/SERVO13") (class "Default")
      (node (ref "H14") (pin "1") (pinfunction "1_1") (pintype "unspecified"))
      (node (ref "U1") (pin "11") (pinfunction "LED5_11") (pintype "unspecified"))
    )
    (net (code "32") (name "/SERVO14") (class "Default")
      (node (ref "H17") (pin "1") (pinfunction "1_1") (pintype "unspecified"))
      (node (ref "U1") (pin "12") (pinfunction "LED6_12") (pintype "unspecified"))
    )
    (net (code "33") (name "/SERVO15") (class "Default")
      (node (ref "H12") (pin "1") (pinfunction "1_1") (pintype "unspecified"))
      (node (ref "U4") (pin "6") (pinfunction "LED0_6") (pintype "unspecified"))
    )
    (net (code "34") (name "/SERVO16") (class "Default")
      (node (ref "H15") (pin "1") (pinfunction "1_1") (pintype "unspecified"))
      (node (ref "U4") (pin "7") (pinfunction "LED1_7") (pintype "unspecified"))
    )
    (net (code "35") (name "/SERVO17") (class "Default")
      (node (ref "H18") (pin "1") (pinfunction "1_1") (pintype "unspecified"))
      (node (ref "U4") (pin "8") (pinfunction "LED2_8") (pintype "unspecified"))
    )
    (net (code "36") (name "/U0_RXD") (class "Default")
      (node (ref "RXD") (pin "1") (pinfunction "K_1") (pintype "unspecified"))
      (node (ref "U5") (pin "2") (pinfunction "TXD_2") (pintype "unspecified"))
      (node (ref "U6") (pin "34") (pinfunction "RXD0_34") (pintype "unspecified"))
    )
    (net (code "37") (name "/U0_TXD") (class "Default")
      (node (ref "TXD") (pin "1") (pinfunction "K_1") (pintype "unspecified"))
      (node (ref "U5") (pin "3") (pinfunction "RXD_3") (pintype "unspecified"))
      (node (ref "U6") (pin "35") (pinfunction "TXD0_35") (pintype "unspecified"))
    )
    (net (code "38") (name "/VOUT1") (class "Default")
      (node (ref "CN2") (pin "1") (pinfunction "1_1") (pintype "unspecified"))
      (node (ref "D3") (pin "1") (pinfunction "C_1") (pintype "unspecified"))
      (node (ref "Q2") (pin "5") (pinfunction "D_5") (pintype "unspecified"))
      (node (ref "Q2") (pin "6") (pinfunction "D_6") (pintype "unspecified"))
      (node (ref "Q2") (pin "7") (pinfunction "D_7") (pintype "unspecified"))
      (node (ref "Q2") (pin "8") (pinfunction "D_8") (pintype "unspecified"))
      (node (ref "Q2") (pin "9") (pinfunction "D_9") (pintype "unspecified"))
    )
    (net (code "39") (name "/VOUT2") (class "Default")
      (node (ref "CN4") (pin "1") (pinfunction "1_1") (pintype "unspecified"))
      (node (ref "D7") (pin "1") (pinfunction "C_1") (pintype "unspecified"))
      (node (ref "Q6") (pin "5") (pinfunction "D_5") (pintype "unspecified"))
      (node (ref "Q6") (pin "6") (pinfunction "D_6") (pintype "unspecified"))
      (node (ref "Q6") (pin "7") (pinfunction "D_7") (pintype "unspecified"))
      (node (ref "Q6") (pin "8") (pinfunction "D_8") (pintype "unspecified"))
      (node (ref "Q6") (pin "9") (pinfunction "D_9") (pintype "unspecified"))
    )
    (net (code "40") (name "/VOUT3") (class "Default")
      (node (ref "CN6") (pin "1") (pinfunction "1_1") (pintype "unspecified"))
      (node (ref "D11") (pin "1") (pinfunction "C_1") (pintype "unspecified"))
      (node (ref "Q10") (pin "5") (pinfunction "D_5") (pintype "unspecified"))
      (node (ref "Q10") (pin "6") (pinfunction "D_6") (pintype "unspecified"))
      (node (ref "Q10") (pin "7") (pinfunction "D_7") (pintype "unspecified"))
      (node (ref "Q10") (pin "8") (pinfunction "D_8") (pintype "unspecified"))
      (node (ref "Q10") (pin "9") (pinfunction "D_9") (pintype "unspecified"))
    )
    (net (code "41") (name "/VOUT4") (class "Default")
      (node (ref "CN8") (pin "1") (pinfunction "1_1") (pintype "unspecified"))
      (node (ref "D15") (pin "1") (pinfunction "C_1") (pintype "unspecified"))
      (node (ref "Q14") (pin "5") (pinfunction "D_5") (pintype "unspecified"))
      (node (ref "Q14") (pin "6") (pinfunction "D_6") (pintype "unspecified"))
      (node (ref "Q14") (pin "7") (pinfunction "D_7") (pintype "unspecified"))
      (node (ref "Q14") (pin "8") (pinfunction "D_8") (pintype "unspecified"))
      (node (ref "Q14") (pin "9") (pinfunction "D_9") (pintype "unspecified"))
    )
    (net (code "42") (name "/VOUT5") (class "Default")
      (node (ref "CN3") (pin "1") (pinfunction "1_1") (pintype "unspecified"))
      (node (ref "D4") (pin "1") (pinfunction "C_1") (pintype "unspecified"))
      (node (ref "Q3") (pin "5") (pinfunction "D_5") (pintype "unspecified"))
      (node (ref "Q3") (pin "6") (pinfunction "D_6") (pintype "unspecified"))
      (node (ref "Q3") (pin "7") (pinfunction "D_7") (pintype "unspecified"))
      (node (ref "Q3") (pin "8") (pinfunction "D_8") (pintype "unspecified"))
      (node (ref "Q3") (pin "9") (pinfunction "D_9") (pintype "unspecified"))
    )
    (net (code "43") (name "/VOUT6") (class "Default")
      (node (ref "CN5") (pin "1") (pinfunction "1_1") (pintype "unspecified"))
      (node (ref "D8") (pin "1") (pinfunction "C_1") (pintype "unspecified"))
      (node (ref "Q7") (pin "5") (pinfunction "D_5") (pintype "unspecified"))
      (node (ref "Q7") (pin "6") (pinfunction "D_6") (pintype "unspecified"))
      (node (ref "Q7") (pin "7") (pinfunction "D_7") (pintype "unspecified"))
      (node (ref "Q7") (pin "8") (pinfunction "D_8") (pintype "unspecified"))
      (node (ref "Q7") (pin "9") (pinfunction "D_9") (pintype "unspecified"))
    )
    (net (code "44") (name "/VOUT7") (class "Default")
      (node (ref "CN7") (pin "1") (pinfunction "1_1") (pintype "unspecified"))
      (node (ref "D12") (pin "1") (pinfunction "C_1") (pintype "unspecified"))
      (node (ref "Q11") (pin "5") (pinfunction "D_5") (pintype "unspecified"))
      (node (ref "Q11") (pin "6") (pinfunction "D_6") (pintype "unspecified"))
      (node (ref "Q11") (pin "7") (pinfunction "D_7") (pintype "unspecified"))
      (node (ref "Q11") (pin "8") (pinfunction "D_8") (pintype "unspecified"))
      (node (ref "Q11") (pin "9") (pinfunction "D_9") (pintype "unspecified"))
    )
    (net (code "45") (name "/VOUT8") (class "Default")
      (node (ref "CN9") (pin "1") (pinfunction "1_1") (pintype "unspecified"))
      (node (ref "D16") (pin "1") (pinfunction "C_1") (pintype "unspecified"))
      (node (ref "Q15") (pin "5") (pinfunction "D_5") (pintype "unspecified"))
      (node (ref "Q15") (pin "6") (pinfunction "D_6") (pintype "unspecified"))
      (node (ref "Q15") (pin "7") (pinfunction "D_7") (pintype "unspecified"))
      (node (ref "Q15") (pin "8") (pinfunction "D_8") (pintype "unspecified"))
      (node (ref "Q15") (pin "9") (pinfunction "D_9") (pintype "unspecified"))
    )
    (net (code "46") (name "3V3") (class "Default")
      (node (ref "C10") (pin "2") (pinfunction "2_2") (pintype "unspecified"))
      (node (ref "C12") (pin "2") (pinfunction "2_2") (pintype "input"))
      (node (ref "C15") (pin "2") (pinfunction "2_2") (pintype "unspecified"))
      (node (ref "C2") (pin "2") (pinfunction "2_2") (pintype "input"))
      (node (ref "C25") (pin "1") (pinfunction "1_1") (pintype "input"))
      (node (ref "C27") (pin "2") (pinfunction "2_2") (pintype "unspecified"))
      (node (ref "C32") (pin "1") (pinfunction "1_1") (pintype "input"))
      (node (ref "C9") (pin "2") (pinfunction "2_2") (pintype "input"))
      (node (ref "R36") (pin "1") (pinfunction "1_1") (pintype "unspecified"))
      (node (ref "R37") (pin "1") (pinfunction "1_1") (pintype "unspecified"))
      (node (ref "R40") (pin "1") (pinfunction "1_1") (pintype "unspecified"))
      (node (ref "U1") (pin "28") (pinfunction "VDD_28") (pintype "unspecified"))
      (node (ref "U3") (pin "2") (pinfunction "VOUT_2") (pintype "unspecified"))
      (node (ref "U3") (pin "4") (pinfunction "VOUT_4") (pintype "unspecified"))
      (node (ref "U4") (pin "28") (pinfunction "VDD_28") (pintype "unspecified"))
      (node (ref "U5") (pin "16") (pinfunction "VCC_16") (pintype "unspecified"))
      (node (ref "U6") (pin "2") (pinfunction "3V3_2") (pintype "unspecified"))
      (node (ref "U7") (pin "13") (pinfunction "VDD_13") (pintype "unspecified"))
      (node (ref "U7") (pin "8") (pinfunction "VLOGIC_8") (pintype "unspecified"))
    )
    (net (code "47") (name "5V") (class "Default")
      (node (ref "C4") (pin "2") (pinfunction "2_2") (pintype "unspecified"))
      (node (ref "C5") (pin "1") (pinfunction "1_1") (pintype "unspecified"))
      (node (ref "C7") (pin "2") (pinfunction "2_2") (pintype "input"))
      (node (ref "C8") (pin "2") (pinfunction "2_2") (pintype "unspecified"))
      (node (ref "H1") (pin "2") (pinfunction "2_2") (pintype "unspecified"))
      (node (ref "H10") (pin "2") (pinfunction "2_2") (pintype "unspecified"))
      (node (ref "H11") (pin "2") (pinfunction "2_2") (pintype "unspecified"))
      (node (ref "H12") (pin "2") (pinfunction "2_2") (pintype "unspecified"))
      (node (ref "H13") (pin "2") (pinfunction "2_2") (pintype "unspecified"))
      (node (ref "H14") (pin "2") (pinfunction "2_2") (pintype "unspecified"))
      (node (ref "H15") (pin "2") (pinfunction "2_2") (pintype "unspecified"))
      (node (ref "H16") (pin "2") (pinfunction "2_2") (pintype "unspecified"))
      (node (ref "H17") (pin "2") (pinfunction "2_2") (pintype "unspecified"))
      (node (ref "H18") (pin "2") (pinfunction "2_2") (pintype "unspecified"))
      (node (ref "H2") (pin "2") (pinfunction "2_2") (pintype "unspecified"))
      (node (ref "H3") (pin "2") (pinfunction "2_2") (pintype "unspecified"))
      (node (ref "H4") (pin "2") (pinfunction "2_2") (pintype "unspecified"))
      (node (ref "H5") (pin "2") (pinfunction "2_2") (pintype "unspecified"))
      (node (ref "H6") (pin "2") (pinfunction "2_2") (pintype "unspecified"))
      (node (ref "H7") (pin "2") (pinfunction "2_2") (pintype "unspecified"))
      (node (ref "H8") (pin "2") (pinfunction "2_2") (pintype "unspecified"))
      (node (ref "H9") (pin "2") (pinfunction "2_2") (pintype "unspecified"))
      (node (ref "L1") (pin "2") (pinfunction "2_2") (pintype "unspecified"))
      (node (ref "R7") (pin "2") (pinfunction "2_2") (pintype "unspecified"))
      (node (ref "U3") (pin "3") (pinfunction "VIN_3") (pintype "unspecified"))
      (node (ref "USB1") (pin "A4B9") (pinfunction "VBUS_A4B9") (pintype "unspecified"))
      (node (ref "USB1") (pin "B4A9") (pinfunction "VBUS_B4A9") (pintype "unspecified"))
    )
    (net (code "48") (name "GND") (class "Default")
      (node (ref "3V3") (pin "1") (pinfunction "K_1") (pintype "unspecified"))
      (node (ref "BOOT1") (pin "2") (pinfunction "2_2") (pintype "unspecified"))
      (node (ref "C10") (pin "1") (pinfunction "1_1") (pintype "unspecified"))
      (node (ref "C11") (pin "1") (pinfunction "1_1") (pintype "unspecified"))
      (node (ref "C12") (pin "1") (pinfunction "1_1") (pintype "input"))
      (node (ref "C14") (pin "1") (pinfunction "1_1") (pintype "unspecified"))
      (node (ref "C15") (pin "1") (pinfunction "1_1") (pintype "unspecified"))
      (node (ref "C16") (pin "1") (pinfunction "1_1") (pintype "unspecified"))
      (node (ref "C17") (pin "1") (pinfunction "1_1") (pintype "unspecified"))
      (node (ref "C2") (pin "1") (pinfunction "1_1") (pintype "input"))
      (node (ref "C20") (pin "1") (pinfunction "1_1") (pintype "unspecified"))
      (node (ref "C21") (pin "1") (pinfunction "1_1") (pintype "unspecified"))
      (node (ref "C24") (pin "2") (pinfunction "2_2") (pintype "input"))
      (node (ref "C25") (pin "2") (pinfunction "2_2") (pintype "input"))
      (node (ref "C26") (pin "1") (pinfunction "1_1") (pintype "unspecified"))
      (node (ref "C27") (pin "1") (pinfunction "1_1") (pintype "unspecified"))
      (node (ref "C28") (pin "1") (pinfunction "1_1") (pintype "unspecified"))
      (node (ref "C29") (pin "1") (pinfunction "1_1") (pintype "unspecified"))
      (node (ref "C32") (pin "2") (pinfunction "2_2") (pintype "input"))
      (node (ref "C33") (pin "1") (pinfunction "1_1") (pintype "unspecified"))
      (node (ref "C34") (pin "1") (pinfunction "1_1") (pintype "unspecified"))
      (node (ref "C35") (pin "1") (pinfunction "1_1") (pintype "unspecified"))
      (node (ref "C36") (pin "1") (pinfunction "1_1") (pintype "unspecified"))
      (node (ref "C4") (pin "1") (pinfunction "1_1") (pintype "unspecified"))
      (node (ref "C5") (pin "2") (pinfunction "2_2") (pintype "unspecified"))
      (node (ref "C6") (pin "2") (pinfunction "2_2") (pintype "unspecified"))
      (node (ref "C7") (pin "1") (pinfunction "1_1") (pintype "input"))
      (node (ref "C8") (pin "1") (pinfunction "1_1") (pintype "unspecified"))
      (node (ref "C9") (pin "1") (pinfunction "1_1") (pintype "input"))
      (node (ref "CN7") (pin "2") (pinfunction "2_2") (pintype "unspecified"))
      (node (ref "CN9") (pin "2") (pinfunction "2_2") (pintype "unspecified"))
      (node (ref "D1") (pin "2") (pinfunction "A_2") (pintype "unspecified"))
      (node (ref "D12") (pin "2") (pinfunction "A_2") (pintype "unspecified"))
      (node (ref "D16") (pin "2") (pinfunction "A_2") (pintype "unspecified"))
      (node (ref "EN") (pin "2") (pinfunction "2_2") (pintype "unspecified"))
      (node (ref "Q12") (pin "2") (pinfunction "E_2") (pintype "unspecified"))
      (node (ref "Q13") (pin "2") (pinfunction "E_2") (pintype "unspecified"))
      (node (ref "Q16") (pin "2") (pinfunction "E_2") (pintype "unspecified"))
      (node (ref "Q17") (pin "2") (pinfunction "E_2") (pintype "unspecified"))
      (node (ref "Q4") (pin "2") (pinfunction "E_2") (pintype "unspecified"))
      (node (ref "Q5") (pin "2") (pinfunction "E_2") (pintype "unspecified"))
      (node (ref "Q8") (pin "2") (pinfunction "E_2") (pintype "unspecified"))
      (node (ref "Q9") (pin "2") (pinfunction "E_2") (pintype "unspecified"))
      (node (ref "R1") (pin "2") (pinfunction "2_2") (pintype "input"))
      (node (ref "R10") (pin "2") (pinfunction "2_2") (pintype "unspecified"))
      (node (ref "R11") (pin "2") (pinfunction "2_2") (pintype "unspecified"))
      (node (ref "R14") (pin "1") (pinfunction "1_1") (pintype "input"))
      (node (ref "R15") (pin "1") (pinfunction "1_1") (pintype "input"))
      (node (ref "R2") (pin "2") (pinfunction "2_2") (pintype "input"))
      (node (ref "R22") (pin "1") (pinfunction "1_1") (pintype "input"))
      (node (ref "R23") (pin "1") (pinfunction "1_1") (pintype "input"))
      (node (ref "R3") (pin "2") (pinfunction "2_2") (pintype "input"))
      (node (ref "R30") (pin "1") (pinfunction "1_1") (pintype "input"))
      (node (ref "R31") (pin "1") (pinfunction "1_1") (pintype "input"))
      (node (ref "R4") (pin "2") (pinfunction "2_2") (pintype "input"))
      (node (ref "R41") (pin "1") (pinfunction "1_1") (pintype "input"))
      (node (ref "R42") (pin "1") (pinfunction "1_1") (pintype "input"))
      (node (ref "R6") (pin "2") (pinfunction "2_2") (pintype "input"))
      (node (ref "R8") (pin "2") (pinfunction "2_2") (pintype "input"))
      (node (ref "R9") (pin "2") (pinfunction "2_2") (pintype "input"))
      (node (ref "RN2") (pin "5") (pinfunction "5_5") (pintype "input"))
      (node (ref "U1") (pin "1") (pinfunction "A0_1") (pintype "unspecified"))
      (node (ref "U1") (pin "14") (pinfunction "VSS_14") (pintype "unspecified"))
      (node (ref "U1") (pin "2") (pinfunction "A1_2") (pintype "unspecified"))
      (node (ref "U1") (pin "24") (pinfunction "A5_24") (pintype "unspecified"))
      (node (ref "U1") (pin "25") (pinfunction "EXTCLK_25") (pintype "unspecified"))
      (node (ref "U1") (pin "3") (pinfunction "A2_3") (pintype "unspecified"))
      (node (ref "U1") (pin "4") (pinfunction "A3_4") (pintype "unspecified"))
      (node (ref "U1") (pin "5") (pinfunction "A4_5") (pintype "unspecified"))
      (node (ref "U2") (pin "5") (pinfunction "GND_5") (pintype "unspecified"))
      (node (ref "U2") (pin "9") (pinfunction "EP_9") (pintype "unspecified"))
      (node (ref "U3") (pin "1") (pinfunction "GND_1") (pintype "unspecified"))
      (node (ref "U4") (pin "1") (pinfunction "A0_1") (pintype "unspecified"))
      (node (ref "U4") (pin "14") (pinfunction "VSS_14") (pintype "unspecified"))
      (node (ref "U4") (pin "2") (pinfunction "A1_2") (pintype "unspecified"))
      (node (ref "U4") (pin "24") (pinfunction "A5_24") (pintype "unspecified"))
      (node (ref "U4") (pin "25") (pinfunction "EXTCLK_25") (pintype "unspecified"))
      (node (ref "U4") (pin "3") (pinfunction "A2_3") (pintype "unspecified"))
      (node (ref "U4") (pin "4") (pinfunction "A3_4") (pintype "unspecified"))
      (node (ref "U4") (pin "5") (pinfunction "A4_5") (pintype "unspecified"))
      (node (ref "U5") (pin "1") (pinfunction "GND_1") (pintype "unspecified"))
      (node (ref "U6") (pin "1") (pinfunction "GND_1") (pintype "unspecified"))
      (node (ref "U6") (pin "15") (pinfunction "GND_15") (pintype "unspecified"))
      (node (ref "U6") (pin "38") (pinfunction "GND_38") (pintype "unspecified"))
      (node (ref "U6") (pin "39") (pinfunction "GND_39") (pintype "unspecified"))
      (node (ref "U7") (pin "1") (pinfunction "CLKIN_1") (pintype "unspecified"))
      (node (ref "U7") (pin "11") (pinfunction "FSYNC_11") (pintype "unspecified"))
      (node (ref "U7") (pin "14") (pinfunction "NC_14") (pintype "unspecified"))
      (node (ref "U7") (pin "15") (pinfunction "NC_15") (pintype "unspecified"))
      (node (ref "U7") (pin "16") (pinfunction "NC_16") (pintype "unspecified"))
      (node (ref "U7") (pin "17") (pinfunction "NC_17") (pintype "unspecified"))
      (node (ref "U7") (pin "18") (pinfunction "GND_18") (pintype "unspecified"))
      (node (ref "U7") (pin "2") (pinfunction "NC_2") (pintype "unspecified"))
      (node (ref "U7") (pin "25") (pinfunction "EP_25") (pintype "unspecified"))
      (node (ref "U7") (pin "3") (pinfunction "NC_3") (pintype "unspecified"))
      (node (ref "U7") (pin "4") (pinfunction "NC_4") (pintype "unspecified"))
      (node (ref "U7") (pin "5") (pinfunction "NC_5") (pintype "unspecified"))
      (node (ref "U7") (pin "9") (pinfunction "AD0_9") (pintype "unspecified"))
      (node (ref "USB1") (pin "1") (pinfunction "SHELL_1") (pintype "unspecified"))
      (node (ref "USB1") (pin "2") (pinfunction "SHELL_2") (pintype "unspecified"))
      (node (ref "USB1") (pin "3") (pinfunction "SHELL_3") (pintype "unspecified"))
      (node (ref "USB1") (pin "4") (pinfunction "SHELL_4") (pintype "unspecified"))
      (node (ref "USB1") (pin "A1B12") (pinfunction "GND_A1B12") (pintype "unspecified"))
      (node (ref "USB1") (pin "B1A12") (pinfunction "GND_B1A12") (pintype "unspecified"))
    )
    (net (code "49") (name "Net-(3V3-A)") (class "Default")
      (node (ref "3V3") (pin "2") (pinfunction "A_2") (pintype "unspecified"))
      (node (ref "BOOT") (pin "2") (pinfunction "A_2") (pintype "unspecified"))
      (node (ref "R37") (pin "2") (pinfunction "2_2") (pintype "unspecified"))
      (node (ref "RXD") (pin "2") (pinfunction "A_2") (pintype "unspecified"))
      (node (ref "TXD") (pin "2") (pinfunction "A_2") (pintype "unspecified"))
    )
    (net (code "50") (name "Net-(C1-Pad1)") (class "Default")
      (node (ref "C1") (pin "1") (pinfunction "1_1") (pintype "input"))
      (node (ref "R1") (pin "1") (pinfunction "1_1") (pintype "input"))
    )
    (net (code "51") (name "Net-(CN1-+)") (class "Default")
      (node (ref "CN1") (pin "2") (pinfunction "+_2") (pintype "unspecified"))
      (node (ref "SW1") (pin "3") (pinfunction "3_3") (pintype "unspecified"))
    )
    (net (code "52") (name "Net-(D1-K)") (class "Default")
      (node (ref "C3") (pin "2") (pinfunction "2_2") (pintype "unspecified"))
      (node (ref "D1") (pin "1") (pinfunction "K_1") (pintype "unspecified"))
      (node (ref "L1") (pin "1") (pinfunction "1_1") (pintype "unspecified"))
      (node (ref "U2") (pin "1") (pinfunction "SW_1") (pintype "unspecified"))
    )
    (net (code "53") (name "Net-(D5-A)") (class "Default")
      (node (ref "C18") (pin "1") (pinfunction "1_1") (pintype "unspecified"))
      (node (ref "D5") (pin "2") (pinfunction "A_2") (pintype "unspecified"))
      (node (ref "Q2") (pin "4") (pinfunction "G_4") (pintype "unspecified"))
      (node (ref "R16") (pin "1") (pinfunction "1_1") (pintype "input"))
      (node (ref "R18") (pin "2") (pinfunction "2_2") (pintype "input"))
    )
    (net (code "54") (name "Net-(D6-A)") (class "Default")
      (node (ref "C19") (pin "1") (pinfunction "1_1") (pintype "unspecified"))
      (node (ref "D6") (pin "2") (pinfunction "A_2") (pintype "unspecified"))
      (node (ref "Q3") (pin "4") (pinfunction "G_4") (pintype "unspecified"))
      (node (ref "R17") (pin "1") (pinfunction "1_1") (pintype "input"))
      (node (ref "R19") (pin "2") (pinfunction "2_2") (pintype "input"))
    )
    (net (code "55") (name "Net-(D9-A)") (class "Default")
      (node (ref "C22") (pin "1") (pinfunction "1_1") (pintype "unspecified"))
      (node (ref "D9") (pin "2") (pinfunction "A_2") (pintype "unspecified"))
      (node (ref "Q6") (pin "4") (pinfunction "G_4") (pintype "unspecified"))
      (node (ref "R24") (pin "1") (pinfunction "1_1") (pintype "input"))
      (node (ref "R26") (pin "2") (pinfunction "2_2") (pintype "input"))
    )
    (net (code "56") (name "Net-(D10-A)") (class "Default")
      (node (ref "C23") (pin "1") (pinfunction "1_1") (pintype "unspecified"))
      (node (ref "D10") (pin "2") (pinfunction "A_2") (pintype "unspecified"))
      (node (ref "Q7") (pin "4") (pinfunction "G_4") (pintype "unspecified"))
      (node (ref "R25") (pin "1") (pinfunction "1_1") (pintype "input"))
      (node (ref "R27") (pin "2") (pinfunction "2_2") (pintype "input"))
    )
    (net (code "57") (name "Net-(D13-A)") (class "Default")
      (node (ref "C30") (pin "1") (pinfunction "1_1") (pintype "unspecified"))
      (node (ref "D13") (pin "2") (pinfunction "A_2") (pintype "unspecified"))
      (node (ref "Q10") (pin "4") (pinfunction "G_4") (pintype "unspecified"))
      (node (ref "R32") (pin "1") (pinfunction "1_1") (pintype "input"))
      (node (ref "R34") (pin "2") (pinfunction "2_2") (pintype "input"))
    )
    (net (code "58") (name "Net-(D14-A)") (class "Default")
      (node (ref "C31") (pin "1") (pinfunction "1_1") (pintype "unspecified"))
      (node (ref "D14") (pin "2") (pinfunction "A_2") (pintype "unspecified"))
      (node (ref "Q11") (pin "4") (pinfunction "G_4") (pintype "unspecified"))
      (node (ref "R33") (pin "1") (pinfunction "1_1") (pintype "input"))
      (node (ref "R35") (pin "2") (pinfunction "2_2") (pintype "input"))
    )
    (net (code "59") (name "Net-(D17-A)") (class "Default")
      (node (ref "C37") (pin "1") (pinfunction "1_1") (pintype "unspecified"))
      (node (ref "D17") (pin "2") (pinfunction "A_2") (pintype "unspecified"))
      (node (ref "Q14") (pin "4") (pinfunction "G_4") (pintype "unspecified"))
      (node (ref "R43") (pin "1") (pinfunction "1_1") (pintype "input"))
      (node (ref "R45") (pin "2") (pinfunction "2_2") (pintype "input"))
    )
    (net (code "60") (name "Net-(D18-A)") (class "Default")
      (node (ref "C38") (pin "1") (pinfunction "1_1") (pintype "unspecified"))
      (node (ref "D18") (pin "2") (pinfunction "A_2") (pintype "unspecified"))
      (node (ref "Q15") (pin "4") (pinfunction "G_4") (pintype "unspecified"))
      (node (ref "R44") (pin "1") (pinfunction "1_1") (pintype "input"))
      (node (ref "R46") (pin "2") (pinfunction "2_2") (pintype "input"))
    )
    (net (code "61") (name "Net-(Q4-B)") (class "Default")
      (node (ref "Q4") (pin "1") (pinfunction "B_1") (pintype "unspecified"))
      (node (ref "R12") (pin "1") (pinfunction "1_1") (pintype "unspecified"))
      (node (ref "R14") (pin "2") (pinfunction "2_2") (pintype "input"))
    )
    (net (code "62") (name "Net-(Q4-C)") (class "Default")
      (node (ref "Q4") (pin "3") (pinfunction "C_3") (pintype "unspecified"))
      (node (ref "R18") (pin "1") (pinfunction "1_1") (pintype "input"))
    )
    (net (code "63") (name "Net-(Q5-B)") (class "Default")
      (node (ref "Q5") (pin "1") (pinfunction "B_1") (pintype "unspecified"))
      (node (ref "R13") (pin "1") (pinfunction "1_1") (pintype "unspecified"))
      (node (ref "R15") (pin "2") (pinfunction "2_2") (pintype "input"))
    )
    (net (code "64") (name "Net-(Q5-C)") (class "Default")
      (node (ref "Q5") (pin "3") (pinfunction "C_3") (pintype "unspecified"))
      (node (ref "R19") (pin "1") (pinfunction "1_1") (pintype "input"))
    )
    (net (code "65") (name "Net-(Q8-B)") (class "Default")
      (node (ref "Q8") (pin "1") (pinfunction "B_1") (pintype "unspecified"))
      (node (ref "R20") (pin "1") (pinfunction "1_1") (pintype "unspecified"))
      (node (ref "R22") (pin "2") (pinfunction "2_2") (pintype "input"))
    )
    (net (code "66") (name "Net-(Q8-C)") (class "Default")
      (node (ref "Q8") (pin "3") (pinfunction "C_3") (pintype "unspecified"))
      (node (ref "R26") (pin "1") (pinfunction "1_1") (pintype "input"))
    )
    (net (code "67") (name "Net-(Q9-B)") (class "Default")
      (node (ref "Q9") (pin "1") (pinfunction "B_1") (pintype "unspecified"))
      (node (ref "R21") (pin "1") (pinfunction "1_1") (pintype "unspecified"))
      (node (ref "R23") (pin "2") (pinfunction "2_2") (pintype "input"))
    )
    (net (code "68") (name "Net-(Q9-C)") (class "Default")
      (node (ref "Q9") (pin "3") (pinfunction "C_3") (pintype "unspecified"))
      (node (ref "R27") (pin "1") (pinfunction "1_1") (pintype "input"))
    )
    (net (code "69") (name "Net-(Q12-B)") (class "Default")
      (node (ref "Q12") (pin "1") (pinfunction "B_1") (pintype "unspecified"))
      (node (ref "R28") (pin "1") (pinfunction "1_1") (pintype "unspecified"))
      (node (ref "R30") (pin "2") (pinfunction "2_2") (pintype "input"))
    )
    (net (code "70") (name "Net-(Q12-C)") (class "Default")
      (node (ref "Q12") (pin "3") (pinfunction "C_3") (pintype "unspecified"))
      (node (ref "R34") (pin "1") (pinfunction "1_1") (pintype "input"))
    )
    (net (code "71") (name "Net-(Q13-B)") (class "Default")
      (node (ref "Q13") (pin "1") (pinfunction "B_1") (pintype "unspecified"))
      (node (ref "R29") (pin "1") (pinfunction "1_1") (pintype "unspecified"))
      (node (ref "R31") (pin "2") (pinfunction "2_2") (pintype "input"))
    )
    (net (code "72") (name "Net-(Q13-C)") (class "Default")
      (node (ref "Q13") (pin "3") (pinfunction "C_3") (pintype "unspecified"))
      (node (ref "R35") (pin "1") (pinfunction "1_1") (pintype "input"))
    )
    (net (code "73") (name "Net-(Q16-B)") (class "Default")
      (node (ref "Q16") (pin "1") (pinfunction "B_1") (pintype "unspecified"))
      (node (ref "R38") (pin "1") (pinfunction "1_1") (pintype "unspecified"))
      (node (ref "R41") (pin "2") (pinfunction "2_2") (pintype "input"))
    )
    (net (code "74") (name "Net-(Q16-C)") (class "Default")
      (node (ref "Q16") (pin "3") (pinfunction "C_3") (pintype "unspecified"))
      (node (ref "R45") (pin "1") (pinfunction "1_1") (pintype "input"))
    )
    (net (code "75") (name "Net-(Q17-B)") (class "Default")
      (node (ref "Q17") (pin "1") (pinfunction "B_1") (pintype "unspecified"))
      (node (ref "R39") (pin "1") (pinfunction "1_1") (pintype "unspecified"))
      (node (ref "R42") (pin "2") (pinfunction "2_2") (pintype "input"))
    )
    (net (code "76") (name "Net-(Q17-C)") (class "Default")
      (node (ref "Q17") (pin "3") (pinfunction "C_3") (pintype "unspecified"))
      (node (ref "R46") (pin "1") (pinfunction "1_1") (pintype "input"))
    )
    (net (code "77") (name "Net-(RN1-Pad1)") (class "Default")
      (node (ref "RN1") (pin "1") (pinfunction "1_1") (pintype "input"))
      (node (ref "RN1") (pin "2") (pinfunction "2_2") (pintype "input"))
    )
    (net (code "78") (name "Net-(RN1-Pad3)") (class "Default")
      (node (ref "RN1") (pin "3") (pinfunction "3_3") (pintype "input"))
      (node (ref "RN1") (pin "4") (pinfunction "4_4") (pintype "input"))
    )
    (net (code "79") (name "Net-(RN1-Pad5)") (class "Default")
      (node (ref "RN1") (pin "5") (pinfunction "5_5") (pintype "input"))
      (node (ref "RN2") (pin "8") (pinfunction "8_8") (pintype "input"))
    )
    (net (code "80") (name "Net-(RN1-Pad6)") (class "Default")
      (node (ref "RN1") (pin "6") (pinfunction "6_6") (pintype "input"))
      (node (ref "RN1") (pin "7") (pinfunction "7_7") (pintype "input"))
    )
    (net (code "81") (name "Net-(RN2-Pad1)") (class "Default")
      (node (ref "RN2") (pin "1") (pinfunction "1_1") (pintype "input"))
      (node (ref "RN2") (pin "2") (pinfunction "2_2") (pintype "input"))
    )
    (net (code "82") (name "Net-(RN2-Pad6)") (class "Default")
      (node (ref "RN2") (pin "6") (pinfunction "6_6") (pintype "input"))
      (node (ref "RN2") (pin "7") (pinfunction "7_7") (pintype "input"))
    )
    (net (code "83") (name "Net-(U1-OE#)") (class "Default")
      (node (ref "R2") (pin "1") (pinfunction "1_1") (pintype "input"))
      (node (ref "U1") (pin "23") (pinfunction "OE#_23") (pintype "unspecified"))
    )
    (net (code "84") (name "Net-(U2-BST)") (class "Default")
      (node (ref "C3") (pin "1") (pinfunction "1_1") (pintype "unspecified"))
      (node (ref "U2") (pin "8") (pinfunction "BST_8") (pintype "unspecified"))
    )
    (net (code "85") (name "Net-(U2-COMP)") (class "Default")
      (node (ref "C1") (pin "2") (pinfunction "2_2") (pintype "input"))
      (node (ref "U2") (pin "3") (pinfunction "COMP_3") (pintype "unspecified"))
    )
    (net (code "86") (name "Net-(U2-EN)") (class "Default")
      (node (ref "R5") (pin "1") (pinfunction "1_1") (pintype "input"))
      (node (ref "R6") (pin "1") (pinfunction "1_1") (pintype "input"))
      (node (ref "U2") (pin "2") (pinfunction "EN_2") (pintype "unspecified"))
    )
    (net (code "87") (name "Net-(U2-FB)") (class "Default")
      (node (ref "R3") (pin "1") (pinfunction "1_1") (pintype "input"))
      (node (ref "R7") (pin "1") (pinfunction "1_1") (pintype "unspecified"))
      (node (ref "U2") (pin "4") (pinfunction "FB_4") (pintype "unspecified"))
    )
    (net (code "88") (name "Net-(U2-FREQ)") (class "Default")
      (node (ref "R4") (pin "1") (pinfunction "1_1") (pintype "input"))
      (node (ref "U2") (pin "6") (pinfunction "FREQ_6") (pintype "unspecified"))
    )
    (net (code "89") (name "Net-(U4-OE#)") (class "Default")
      (node (ref "R8") (pin "1") (pinfunction "1_1") (pintype "input"))
      (node (ref "U4") (pin "23") (pinfunction "OE#_23") (pintype "unspecified"))
    )
    (net (code "90") (name "Net-(U5-V3)") (class "Default")
      (node (ref "C14") (pin "2") (pinfunction "2_2") (pintype "unspecified"))
      (node (ref "U5") (pin "4") (pinfunction "V3_4") (pintype "unspecified"))
    )
    (net (code "91") (name "Net-(U7-CPOUT)") (class "Default")
      (node (ref "C24") (pin "1") (pinfunction "1_1") (pintype "input"))
      (node (ref "U7") (pin "20") (pinfunction "CPOUT_20") (pintype "unspecified"))
    )
    (net (code "92") (name "Net-(U7-REGOUT)") (class "Default")
      (node (ref "C26") (pin "2") (pinfunction "2_2") (pintype "unspecified"))
      (node (ref "U7") (pin "10") (pinfunction "REGOUT_10") (pintype "unspecified"))
    )
    (net (code "93") (name "Net-(USB1-CC1)") (class "Default")
      (node (ref "R10") (pin "1") (pinfunction "1_1") (pintype "unspecified"))
      (node (ref "USB1") (pin "A5") (pinfunction "CC1_A5") (pintype "unspecified"))
    )
    (net (code "94") (name "Net-(USB1-CC2)") (class "Default")
      (node (ref "R11") (pin "1") (pinfunction "1_1") (pintype "unspecified"))
      (node (ref "USB1") (pin "B5") (pinfunction "CC2_B5") (pintype "unspecified"))
    )
    (net (code "95") (name "PGND") (class "Default")
      (node (ref "C13") (pin "2") (pinfunction "2_2") (pintype "input"))
      (node (ref "CN1") (pin "1") (pinfunction "-_1") (pintype "unspecified"))
      (node (ref "CN1") (pin "3") (pinfunction "3_3") (pintype "unspecified"))
      (node (ref "CN1") (pin "4") (pinfunction "4_4") (pintype "unspecified"))
      (node (ref "CN2") (pin "2") (pinfunction "2_2") (pintype "unspecified"))
      (node (ref "CN3") (pin "2") (pinfunction "2_2") (pintype "unspecified"))
      (node (ref "CN4") (pin "2") (pinfunction "2_2") (pintype "unspecified"))
      (node (ref "CN5") (pin "2") (pinfunction "2_2") (pintype "unspecified"))
      (node (ref "CN6") (pin "2") (pinfunction "2_2") (pintype "unspecified"))
      (node (ref "CN8") (pin "2") (pinfunction "2_2") (pintype "unspecified"))
      (node (ref "D11") (pin "2") (pinfunction "A_2") (pintype "unspecified"))
      (node (ref "D15") (pin "2") (pinfunction "A_2") (pintype "unspecified"))
      (node (ref "D2") (pin "2") (pinfunction "A_2") (pintype "unspecified"))
      (node (ref "D3") (pin "2") (pinfunction "A_2") (pintype "unspecified"))
      (node (ref "D4") (pin "2") (pinfunction "A_2") (pintype "unspecified"))
      (node (ref "D7") (pin "2") (pinfunction "A_2") (pintype "unspecified"))
      (node (ref "D8") (pin "2") (pinfunction "A_2") (pintype "unspecified"))
      (node (ref "H1") (pin "3") (pinfunction "3_3") (pintype "unspecified"))
      (node (ref "H10") (pin "3") (pinfunction "3_3") (pintype "unspecified"))
      (node (ref "H11") (pin "3") (pinfunction "3_3") (pintype "unspecified"))
      (node (ref "H12") (pin "3") (pinfunction "3_3") (pintype "unspecified"))
      (node (ref "H13") (pin "3") (pinfunction "3_3") (pintype "unspecified"))
      (node (ref "H14") (pin "3") (pinfunction "3_3") (pintype "unspecified"))
      (node (ref "H15") (pin "3") (pinfunction "3_3") (pintype "unspecified"))
      (node (ref "H16") (pin "3") (pinfunction "3_3") (pintype "unspecified"))
      (node (ref "H17") (pin "3") (pinfunction "3_3") (pintype "unspecified"))
      (node (ref "H18") (pin "3") (pinfunction "3_3") (pintype "unspecified"))
      (node (ref "H2") (pin "3") (pinfunction "3_3") (pintype "unspecified"))
      (node (ref "H3") (pin "3") (pinfunction "3_3") (pintype "unspecified"))
      (node (ref "H4") (pin "3") (pinfunction "3_3") (pintype "unspecified"))
      (node (ref "H5") (pin "3") (pinfunction "3_3") (pintype "unspecified"))
      (node (ref "H6") (pin "3") (pinfunction "3_3") (pintype "unspecified"))
      (node (ref "H7") (pin "3") (pinfunction "3_3") (pintype "unspecified"))
      (node (ref "H8") (pin "3") (pinfunction "3_3") (pintype "unspecified"))
      (node (ref "H9") (pin "3") (pinfunction "3_3") (pintype "unspecified"))
      (node (ref "R9") (pin "1") (pinfunction "1_1") (pintype "input"))
    )
    (net (code "96") (name "VIN") (class "Default")
      (node (ref "C11") (pin "2") (pinfunction "2_2") (pintype "unspecified"))
      (node (ref "C13") (pin "1") (pinfunction "1_1") (pintype "input"))
      (node (ref "C18") (pin "2") (pinfunction "2_2") (pintype "unspecified"))
      (node (ref "C19") (pin "2") (pinfunction "2_2") (pintype "unspecified"))
      (node (ref "C22") (pin "2") (pinfunction "2_2") (pintype "unspecified"))
      (node (ref "C23") (pin "2") (pinfunction "2_2") (pintype "unspecified"))
      (node (ref "C30") (pin "2") (pinfunction "2_2") (pintype "unspecified"))
      (node (ref "C31") (pin "2") (pinfunction "2_2") (pintype "unspecified"))
      (node (ref "C37") (pin "2") (pinfunction "2_2") (pintype "unspecified"))
      (node (ref "C38") (pin "2") (pinfunction "2_2") (pintype "unspecified"))
      (node (ref "C6") (pin "1") (pinfunction "1_1") (pintype "unspecified"))
      (node (ref "D10") (pin "1") (pinfunction "C_1") (pintype "unspecified"))
      (node (ref "D13") (pin "1") (pinfunction "C_1") (pintype "unspecified"))
      (node (ref "D14") (pin "1") (pinfunction "C_1") (pintype "unspecified"))
      (node (ref "D17") (pin "1") (pinfunction "C_1") (pintype "unspecified"))
      (node (ref "D18") (pin "1") (pinfunction "C_1") (pintype "unspecified"))
      (node (ref "D2") (pin "1") (pinfunction "C_1") (pintype "unspecified"))
      (node (ref "D5") (pin "1") (pinfunction "C_1") (pintype "unspecified"))
      (node (ref "D6") (pin "1") (pinfunction "C_1") (pintype "unspecified"))
      (node (ref "D9") (pin "1") (pinfunction "C_1") (pintype "unspecified"))
      (node (ref "Q10") (pin "1") (pinfunction "S_1") (pintype "unspecified"))
      (node (ref "Q10") (pin "2") (pinfunction "S_2") (pintype "unspecified"))
      (node (ref "Q10") (pin "3") (pinfunction "S_3") (pintype "unspecified"))
      (node (ref "Q11") (pin "1") (pinfunction "S_1") (pintype "unspecified"))
      (node (ref "Q11") (pin "2") (pinfunction "S_2") (pintype "unspecified"))
      (node (ref "Q11") (pin "3") (pinfunction "S_3") (pintype "unspecified"))
      (node (ref "Q14") (pin "1") (pinfunction "S_1") (pintype "unspecified"))
      (node (ref "Q14") (pin "2") (pinfunction "S_2") (pintype "unspecified"))
      (node (ref "Q14") (pin "3") (pinfunction "S_3") (pintype "unspecified"))
      (node (ref "Q15") (pin "1") (pinfunction "S_1") (pintype "unspecified"))
      (node (ref "Q15") (pin "2") (pinfunction "S_2") (pintype "unspecified"))
      (node (ref "Q15") (pin "3") (pinfunction "S_3") (pintype "unspecified"))
      (node (ref "Q2") (pin "1") (pinfunction "S_1") (pintype "unspecified"))
      (node (ref "Q2") (pin "2") (pinfunction "S_2") (pintype "unspecified"))
      (node (ref "Q2") (pin "3") (pinfunction "S_3") (pintype "unspecified"))
      (node (ref "Q3") (pin "1") (pinfunction "S_1") (pintype "unspecified"))
      (node (ref "Q3") (pin "2") (pinfunction "S_2") (pintype "unspecified"))
      (node (ref "Q3") (pin "3") (pinfunction "S_3") (pintype "unspecified"))
      (node (ref "Q6") (pin "1") (pinfunction "S_1") (pintype "unspecified"))
      (node (ref "Q6") (pin "2") (pinfunction "S_2") (pintype "unspecified"))
      (node (ref "Q6") (pin "3") (pinfunction "S_3") (pintype "unspecified"))
      (node (ref "Q7") (pin "1") (pinfunction "S_1") (pintype "unspecified"))
      (node (ref "Q7") (pin "2") (pinfunction "S_2") (pintype "unspecified"))
      (node (ref "Q7") (pin "3") (pinfunction "S_3") (pintype "unspecified"))
      (node (ref "R16") (pin "2") (pinfunction "2_2") (pintype "input"))
      (node (ref "R17") (pin "2") (pinfunction "2_2") (pintype "input"))
      (node (ref "R24") (pin "2") (pinfunction "2_2") (pintype "input"))
      (node (ref "R25") (pin "2") (pinfunction "2_2") (pintype "input"))
      (node (ref "R32") (pin "2") (pinfunction "2_2") (pintype "input"))
      (node (ref "R33") (pin "2") (pinfunction "2_2") (pintype "input"))
      (node (ref "R43") (pin "2") (pinfunction "2_2") (pintype "input"))
      (node (ref "R44") (pin "2") (pinfunction "2_2") (pintype "input"))
      (node (ref "R5") (pin "2") (pinfunction "2_2") (pintype "input"))
      (node (ref "RN1") (pin "8") (pinfunction "8_8") (pintype "input"))
      (node (ref "SW1") (pin "2") (pinfunction "2_2") (pintype "unspecified"))
      (node (ref "U2") (pin "7") (pinfunction "VIN_7") (pintype "unspecified"))
    )
    (net (code "97") (name "unconnected-(CN2-Pad3)") (class "Default")
      (node (ref "CN2") (pin "3") (pinfunction "3_3") (pintype "unspecified+no_connect"))
    )
    (net (code "98") (name "unconnected-(CN2-Pad4)") (class "Default")
      (node (ref "CN2") (pin "4") (pinfunction "4_4") (pintype "unspecified+no_connect"))
    )
    (net (code "99") (name "unconnected-(CN3-Pad3)") (class "Default")
      (node (ref "CN3") (pin "3") (pinfunction "3_3") (pintype "unspecified+no_connect"))
    )
    (net (code "100") (name "unconnected-(CN3-Pad4)") (class "Default")
      (node (ref "CN3") (pin "4") (pinfunction "4_4") (pintype "unspecified+no_connect"))
    )
    (net (code "101") (name "unconnected-(CN4-Pad3)") (class "Default")
      (node (ref "CN4") (pin "3") (pinfunction "3_3") (pintype "unspecified+no_connect"))
    )
    (net (code "102") (name "unconnected-(CN4-Pad4)") (class "Default")
      (node (ref "CN4") (pin "4") (pinfunction "4_4") (pintype "unspecified+no_connect"))
    )
    (net (code "103") (name "unconnected-(CN5-Pad3)") (class "Default")
      (node (ref "CN5") (pin "3") (pinfunction "3_3") (pintype "unspecified+no_connect"))
    )
    (net (code "104") (name "unconnected-(CN5-Pad4)") (class "Default")
      (node (ref "CN5") (pin "4") (pinfunction "4_4") (pintype "unspecified+no_connect"))
    )
    (net (code "105") (name "unconnected-(CN6-Pad3)") (class "Default")
      (node (ref "CN6") (pin "3") (pinfunction "3_3") (pintype "unspecified+no_connect"))
    )
    (net (code "106") (name "unconnected-(CN6-Pad4)") (class "Default")
      (node (ref "CN6") (pin "4") (pinfunction "4_4") (pintype "unspecified+no_connect"))
    )
    (net (code "107") (name "unconnected-(CN7-Pad3)") (class "Default")
      (node (ref "CN7") (pin "3") (pinfunction "3_3") (pintype "unspecified+no_connect"))
    )
    (net (code "108") (name "unconnected-(CN7-Pad4)") (class "Default")
      (node (ref "CN7") (pin "4") (pinfunction "4_4") (pintype "unspecified+no_connect"))
    )
    (net (code "109") (name "unconnected-(CN8-Pad3)") (class "Default")
      (node (ref "CN8") (pin "3") (pinfunction "3_3") (pintype "unspecified+no_connect"))
    )
    (net (code "110") (name "unconnected-(CN8-Pad4)") (class "Default")
      (node (ref "CN8") (pin "4") (pinfunction "4_4") (pintype "unspecified+no_connect"))
    )
    (net (code "111") (name "unconnected-(CN9-Pad3)") (class "Default")
      (node (ref "CN9") (pin "3") (pinfunction "3_3") (pintype "unspecified+no_connect"))
    )
    (net (code "112") (name "unconnected-(CN9-Pad4)") (class "Default")
      (node (ref "CN9") (pin "4") (pinfunction "4_4") (pintype "unspecified+no_connect"))
    )
    (net (code "113") (name "unconnected-(SW1-Pad1)") (class "Default")
      (node (ref "SW1") (pin "1") (pinfunction "1_1") (pintype "unspecified+no_connect"))
    )
    (net (code "114") (name "unconnected-(U1-LED7-Pad13)") (class "Default")
      (node (ref "U1") (pin "13") (pinfunction "LED7_13") (pintype "unspecified"))
    )
    (net (code "115") (name "unconnected-(U4-LED3-Pad9)") (class "Default")
      (node (ref "U4") (pin "9") (pinfunction "LED3_9") (pintype "unspecified+no_connect"))
    )
    (net (code "116") (name "unconnected-(U4-LED4-Pad10)") (class "Default")
      (node (ref "U4") (pin "10") (pinfunction "LED4_10") (pintype "unspecified+no_connect"))
    )
    (net (code "117") (name "unconnected-(U4-LED5-Pad11)") (class "Default")
      (node (ref "U4") (pin "11") (pinfunction "LED5_11") (pintype "unspecified+no_connect"))
    )
    (net (code "118") (name "unconnected-(U4-LED6-Pad12)") (class "Default")
      (node (ref "U4") (pin "12") (pinfunction "LED6_12") (pintype "unspecified+no_connect"))
    )
    (net (code "119") (name "unconnected-(U4-LED7-Pad13)") (class "Default")
      (node (ref "U4") (pin "13") (pinfunction "LED7_13") (pintype "unspecified+no_connect"))
    )
    (net (code "120") (name "unconnected-(U4-LED8-Pad15)") (class "Default")
      (node (ref "U4") (pin "15") (pinfunction "LED8_15") (pintype "unspecified+no_connect"))
    )
    (net (code "121") (name "unconnected-(U4-LED9-Pad16)") (class "Default")
      (node (ref "U4") (pin "16") (pinfunction "LED9_16") (pintype "unspecified+no_connect"))
    )
    (net (code "122") (name "unconnected-(U4-LED10-Pad17)") (class "Default")
      (node (ref "U4") (pin "17") (pinfunction "LED10_17") (pintype "unspecified+no_connect"))
    )
    (net (code "123") (name "unconnected-(U4-LED11-Pad18)") (class "Default")
      (node (ref "U4") (pin "18") (pinfunction "LED11_18") (pintype "unspecified+no_connect"))
    )
    (net (code "124") (name "unconnected-(U4-LED12-Pad19)") (class "Default")
      (node (ref "U4") (pin "19") (pinfunction "LED12_19") (pintype "unspecified+no_connect"))
    )
    (net (code "125") (name "unconnected-(U4-LED13-Pad20)") (class "Default")
      (node (ref "U4") (pin "20") (pinfunction "LED13_20") (pintype "unspecified+no_connect"))
    )
    (net (code "126") (name "unconnected-(U4-LED14-Pad21)") (class "Default")
      (node (ref "U4") (pin "21") (pinfunction "LED14_21") (pintype "unspecified+no_connect"))
    )
    (net (code "127") (name "unconnected-(U4-LED15-Pad22)") (class "Default")
      (node (ref "U4") (pin "22") (pinfunction "LED15_22") (pintype "unspecified+no_connect"))
    )
    (net (code "128") (name "unconnected-(U5-CTS#-Pad9)") (class "Default")
      (node (ref "U5") (pin "9") (pinfunction "CTS#_9") (pintype "unspecified+no_connect"))
    )
    (net (code "129") (name "unconnected-(U5-DCD#-Pad12)") (class "Default")
      (node (ref "U5") (pin "12") (pinfunction "DCD#_12") (pintype "unspecified+no_connect"))
    )
    (net (code "130") (name "unconnected-(U5-DSR#-Pad10)") (class "Default")
      (node (ref "U5") (pin "10") (pinfunction "DSR#_10") (pintype "unspecified+no_connect"))
    )
    (net (code "131") (name "unconnected-(U5-NC.-Pad7)") (class "Default")
      (node (ref "U5") (pin "7") (pinfunction "NC._7") (pintype "unspecified+no_connect"))
    )
    (net (code "132") (name "unconnected-(U5-OUT#-Pad8)") (class "Default")
      (node (ref "U5") (pin "8") (pinfunction "OUT#_8") (pintype "unspecified+no_connect"))
    )
    (net (code "133") (name "unconnected-(U5-R232-Pad15)") (class "Default")
      (node (ref "U5") (pin "15") (pinfunction "R232_15") (pintype "unspecified+no_connect"))
    )
    (net (code "134") (name "unconnected-(U5-RI#-Pad11)") (class "Default")
      (node (ref "U5") (pin "11") (pinfunction "RI#_11") (pintype "unspecified+no_connect"))
    )
    (net (code "135") (name "unconnected-(U6-IO2-Pad24)") (class "Default")
      (node (ref "U6") (pin "24") (pinfunction "IO2_24") (pintype "unspecified+no_connect"))
    )
    (net (code "136") (name "unconnected-(U6-IO4-Pad26)") (class "Default")
      (node (ref "U6") (pin "26") (pinfunction "IO4_26") (pintype "unspecified+no_connect"))
    )
    (net (code "137") (name "unconnected-(U6-IO13-Pad16)") (class "Default")
      (node (ref "U6") (pin "16") (pinfunction "IO13_16") (pintype "unspecified+no_connect"))
    )
    (net (code "138") (name "unconnected-(U6-IO15-Pad23)") (class "Default")
      (node (ref "U6") (pin "23") (pinfunction "IO15_23") (pintype "unspecified+no_connect"))
    )
    (net (code "139") (name "unconnected-(U6-IO16-Pad27)") (class "Default")
      (node (ref "U6") (pin "27") (pinfunction "IO16_27") (pintype "unspecified+no_connect"))
    )
    (net (code "140") (name "unconnected-(U6-IO23-Pad37)") (class "Default")
      (node (ref "U6") (pin "37") (pinfunction "IO23_37") (pintype "unspecified+no_connect"))
    )
    (net (code "141") (name "unconnected-(U6-IO32-Pad8)") (class "Default")
      (node (ref "U6") (pin "8") (pinfunction "IO32_8") (pintype "unspecified+no_connect"))
    )
    (net (code "142") (name "unconnected-(U6-IO33-Pad9)") (class "Default")
      (node (ref "U6") (pin "9") (pinfunction "IO33_9") (pintype "unspecified+no_connect"))
    )
    (net (code "143") (name "unconnected-(U6-IO34-Pad6)") (class "Default")
      (node (ref "U6") (pin "6") (pinfunction "IO34_6") (pintype "unspecified+no_connect"))
    )
    (net (code "144") (name "unconnected-(U6-IO35-Pad7)") (class "Default")
      (node (ref "U6") (pin "7") (pinfunction "IO35_7") (pintype "unspecified+no_connect"))
    )
    (net (code "145") (name "unconnected-(U6-NC-Pad17)") (class "Default")
      (node (ref "U6") (pin "17") (pinfunction "NC_17") (pintype "unspecified+no_connect"))
    )
    (net (code "146") (name "unconnected-(U6-NC-Pad18)") (class "Default")
      (node (ref "U6") (pin "18") (pinfunction "NC_18") (pintype "unspecified+no_connect"))
    )
    (net (code "147") (name "unconnected-(U6-NC-Pad19)") (class "Default")
      (node (ref "U6") (pin "19") (pinfunction "NC_19") (pintype "unspecified+no_connect"))
    )
    (net (code "148") (name "unconnected-(U6-NC-Pad20)") (class "Default")
      (node (ref "U6") (pin "20") (pinfunction "NC_20") (pintype "unspecified+no_connect"))
    )
    (net (code "149") (name "unconnected-(U6-NC-Pad21)") (class "Default")
      (node (ref "U6") (pin "21") (pinfunction "NC_21") (pintype "unspecified+no_connect"))
    )
    (net (code "150") (name "unconnected-(U6-NC-Pad22)") (class "Default")
      (node (ref "U6") (pin "22") (pinfunction "NC_22") (pintype "unspecified+no_connect"))
    )
    (net (code "151") (name "unconnected-(U6-NC-Pad32)") (class "Default")
      (node (ref "U6") (pin "32") (pinfunction "NC_32") (pintype "unspecified+no_connect"))
    )
    (net (code "152") (name "unconnected-(U6-SENSOR_VN-Pad5)") (class "Default")
      (node (ref "U6") (pin "5") (pinfunction "SENSOR_VN_5") (pintype "unspecified+no_connect"))
    )
    (net (code "153") (name "unconnected-(U6-SENSOR_VP-Pad4)") (class "Default")
      (node (ref "U6") (pin "4") (pinfunction "SENSOR_VP_4") (pintype "unspecified+no_connect"))
    )
    (net (code "154") (name "unconnected-(U7-AUX_CL-Pad7)") (class "Default")
      (node (ref "U7") (pin "7") (pinfunction "AUX_CL_7") (pintype "unspecified+no_connect"))
    )
    (net (code "155") (name "unconnected-(U7-AUX_DA-Pad6)") (class "Default")
      (node (ref "U7") (pin "6") (pinfunction "AUX_DA_6") (pintype "unspecified+no_connect"))
    )
    (net (code "156") (name "unconnected-(U7-INT-Pad12)") (class "Default")
      (node (ref "U7") (pin "12") (pinfunction "INT_12") (pintype "unspecified+no_connect"))
    )
    (net (code "157") (name "unconnected-(U7-RESV-Pad19)") (class "Default")
      (node (ref "U7") (pin "19") (pinfunction "RESV_19") (pintype "unspecified+no_connect"))
    )
    (net (code "158") (name "unconnected-(U7-RESV-Pad21)") (class "Default")
      (node (ref "U7") (pin "21") (pinfunction "RESV_21") (pintype "unspecified+no_connect"))
    )
    (net (code "159") (name "unconnected-(U7-RESV-Pad22)") (class "Default")
      (node (ref "U7") (pin "22") (pinfunction "RESV_22") (pintype "unspecified+no_connect"))
    )
    (net (code "160") (name "unconnected-(USB1-SBU1-PadA8)") (class "Default")
      (node (ref "USB1") (pin "A8") (pinfunction "SBU1_A8") (pintype "unspecified+no_connect"))
    )
    (net (code "161") (name "unconnected-(USB1-SBU2-PadB8)") (class "Default")
      (node (ref "USB1") (pin "B8") (pinfunction "SBU2_B8") (pintype "unspecified+no_connect"))
    )
  )
)
